# antifamini.net
KiCad netlist of a schematic drawn in EAGLE
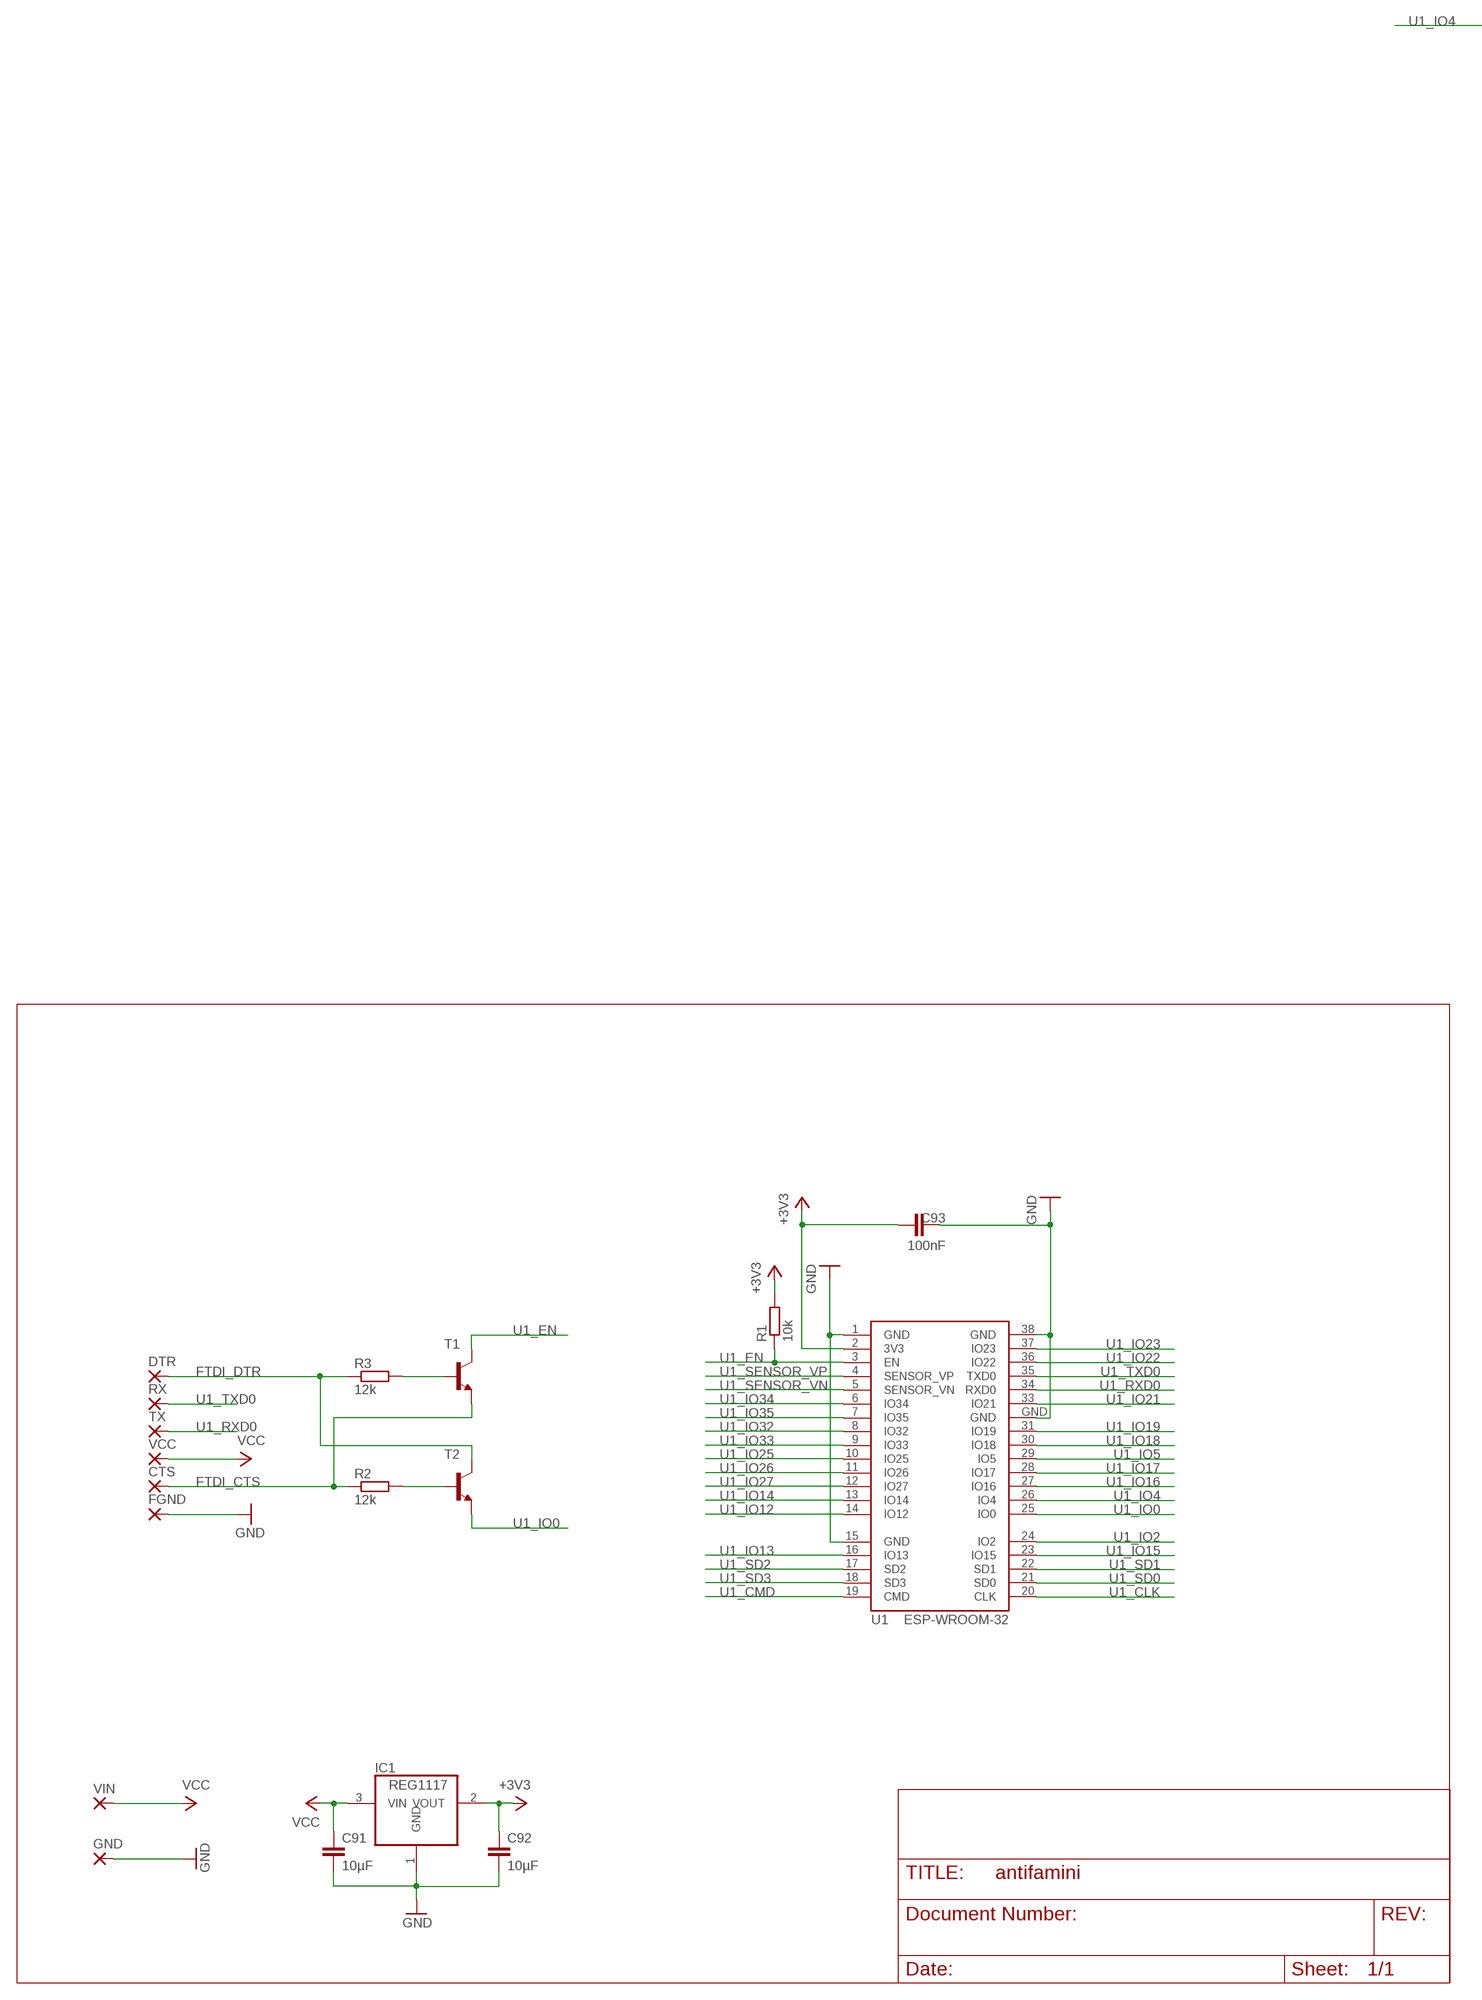
[diagram p0: schematic, sheet 1, part 1 of 2]
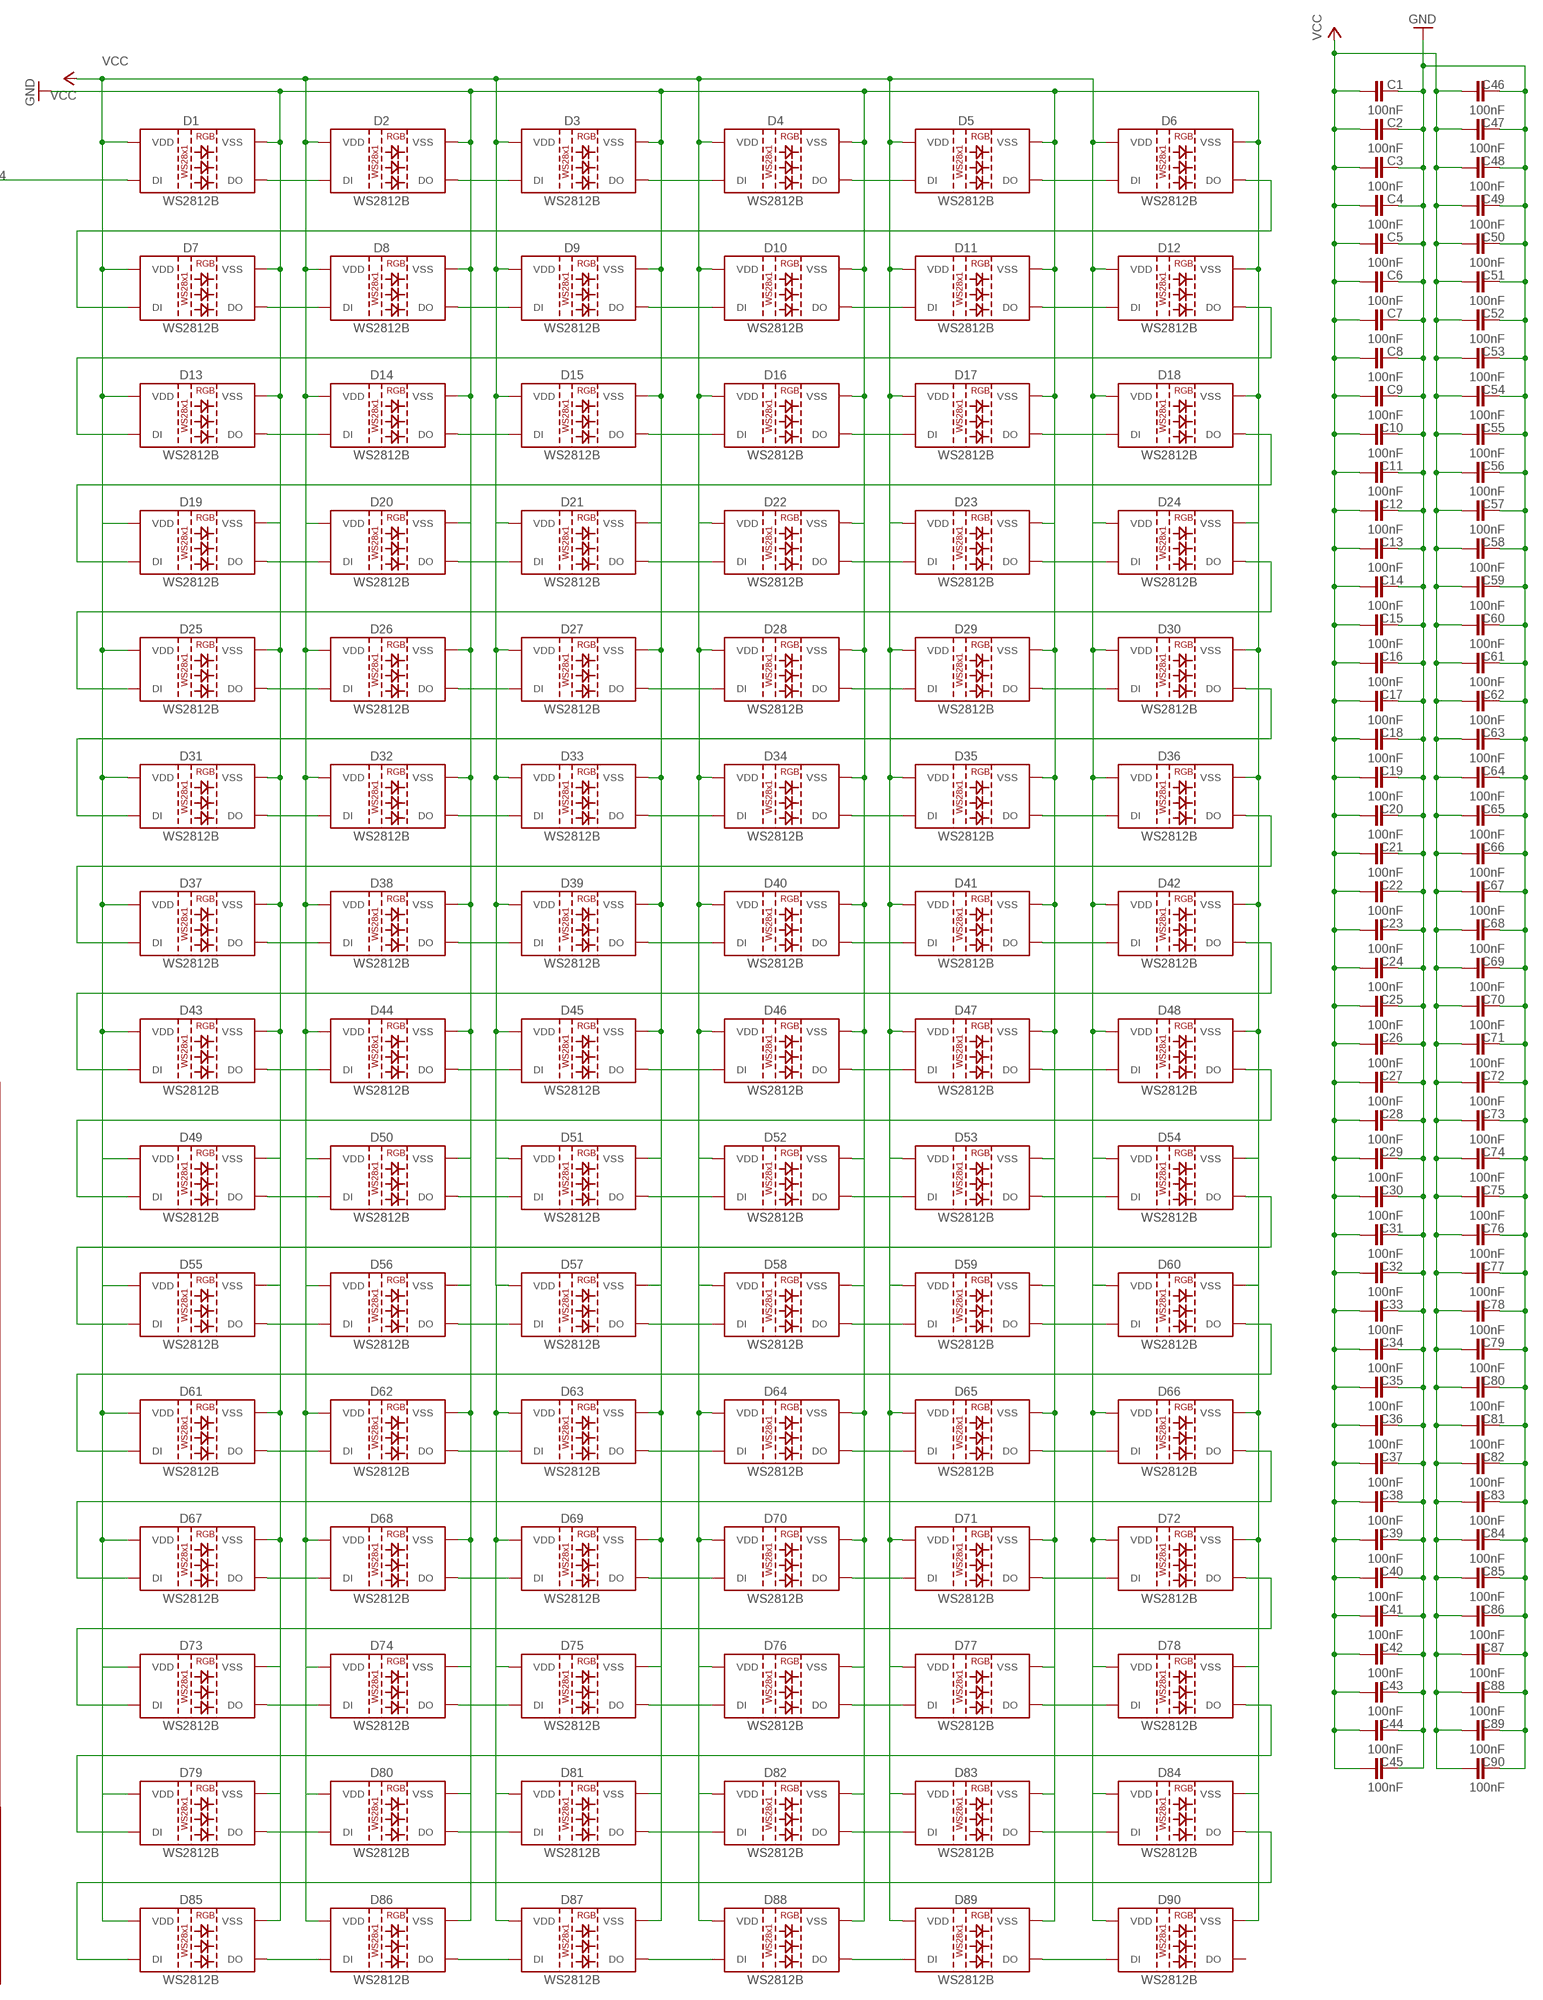
[diagram p1: schematic, sheet 1, part 2 of 2]

(export (version "E")
  (design (tool "Eeschema 10.0.6"))
  (components
    (comp (ref "C1")
      (value "100nF")
      (footprint "eagle-import:C0603")
      (libsource (lib "eagle-import") (part "C-EUC0603"))
    )
    (comp (ref "C2")
      (value "100nF")
      (footprint "eagle-import:C0603")
      (libsource (lib "eagle-import") (part "C-EUC0603"))
    )
    (comp (ref "C3")
      (value "100nF")
      (footprint "eagle-import:C0603")
      (libsource (lib "eagle-import") (part "C-EUC0603"))
    )
    (comp (ref "C4")
      (value "100nF")
      (footprint "eagle-import:C0603")
      (libsource (lib "eagle-import") (part "C-EUC0603"))
    )
    (comp (ref "C5")
      (value "100nF")
      (footprint "eagle-import:C0603")
      (libsource (lib "eagle-import") (part "C-EUC0603"))
    )
    (comp (ref "C6")
      (value "100nF")
      (footprint "eagle-import:C0603")
      (libsource (lib "eagle-import") (part "C-EUC0603"))
    )
    (comp (ref "C7")
      (value "100nF")
      (footprint "eagle-import:C0603")
      (libsource (lib "eagle-import") (part "C-EUC0603"))
    )
    (comp (ref "C8")
      (value "100nF")
      (footprint "eagle-import:C0603")
      (libsource (lib "eagle-import") (part "C-EUC0603"))
    )
    (comp (ref "C9")
      (value "100nF")
      (footprint "eagle-import:C0603")
      (libsource (lib "eagle-import") (part "C-EUC0603"))
    )
    (comp (ref "C10")
      (value "100nF")
      (footprint "eagle-import:C0603")
      (libsource (lib "eagle-import") (part "C-EUC0603"))
    )
    (comp (ref "C11")
      (value "100nF")
      (footprint "eagle-import:C0603")
      (libsource (lib "eagle-import") (part "C-EUC0603"))
    )
    (comp (ref "C12")
      (value "100nF")
      (footprint "eagle-import:C0603")
      (libsource (lib "eagle-import") (part "C-EUC0603"))
    )
    (comp (ref "C13")
      (value "100nF")
      (footprint "eagle-import:C0603")
      (libsource (lib "eagle-import") (part "C-EUC0603"))
    )
    (comp (ref "C14")
      (value "100nF")
      (footprint "eagle-import:C0603")
      (libsource (lib "eagle-import") (part "C-EUC0603"))
    )
    (comp (ref "C15")
      (value "100nF")
      (footprint "eagle-import:C0603")
      (libsource (lib "eagle-import") (part "C-EUC0603"))
    )
    (comp (ref "C16")
      (value "100nF")
      (footprint "eagle-import:C0603")
      (libsource (lib "eagle-import") (part "C-EUC0603"))
    )
    (comp (ref "C17")
      (value "100nF")
      (footprint "eagle-import:C0603")
      (libsource (lib "eagle-import") (part "C-EUC0603"))
    )
    (comp (ref "C18")
      (value "100nF")
      (footprint "eagle-import:C0603")
      (libsource (lib "eagle-import") (part "C-EUC0603"))
    )
    (comp (ref "C19")
      (value "100nF")
      (footprint "eagle-import:C0603")
      (libsource (lib "eagle-import") (part "C-EUC0603"))
    )
    (comp (ref "C20")
      (value "100nF")
      (footprint "eagle-import:C0603")
      (libsource (lib "eagle-import") (part "C-EUC0603"))
    )
    (comp (ref "C21")
      (value "100nF")
      (footprint "eagle-import:C0603")
      (libsource (lib "eagle-import") (part "C-EUC0603"))
    )
    (comp (ref "C22")
      (value "100nF")
      (footprint "eagle-import:C0603")
      (libsource (lib "eagle-import") (part "C-EUC0603"))
    )
    (comp (ref "C23")
      (value "100nF")
      (footprint "eagle-import:C0603")
      (libsource (lib "eagle-import") (part "C-EUC0603"))
    )
    (comp (ref "C24")
      (value "100nF")
      (footprint "eagle-import:C0603")
      (libsource (lib "eagle-import") (part "C-EUC0603"))
    )
    (comp (ref "C25")
      (value "100nF")
      (footprint "eagle-import:C0603")
      (libsource (lib "eagle-import") (part "C-EUC0603"))
    )
    (comp (ref "C26")
      (value "100nF")
      (footprint "eagle-import:C0603")
      (libsource (lib "eagle-import") (part "C-EUC0603"))
    )
    (comp (ref "C27")
      (value "100nF")
      (footprint "eagle-import:C0603")
      (libsource (lib "eagle-import") (part "C-EUC0603"))
    )
    (comp (ref "C28")
      (value "100nF")
      (footprint "eagle-import:C0603")
      (libsource (lib "eagle-import") (part "C-EUC0603"))
    )
    (comp (ref "C29")
      (value "100nF")
      (footprint "eagle-import:C0603")
      (libsource (lib "eagle-import") (part "C-EUC0603"))
    )
    (comp (ref "C30")
      (value "100nF")
      (footprint "eagle-import:C0603")
      (libsource (lib "eagle-import") (part "C-EUC0603"))
    )
    (comp (ref "C31")
      (value "100nF")
      (footprint "eagle-import:C0603")
      (libsource (lib "eagle-import") (part "C-EUC0603"))
    )
    (comp (ref "C32")
      (value "100nF")
      (footprint "eagle-import:C0603")
      (libsource (lib "eagle-import") (part "C-EUC0603"))
    )
    (comp (ref "C33")
      (value "100nF")
      (footprint "eagle-import:C0603")
      (libsource (lib "eagle-import") (part "C-EUC0603"))
    )
    (comp (ref "C34")
      (value "100nF")
      (footprint "eagle-import:C0603")
      (libsource (lib "eagle-import") (part "C-EUC0603"))
    )
    (comp (ref "C35")
      (value "100nF")
      (footprint "eagle-import:C0603")
      (libsource (lib "eagle-import") (part "C-EUC0603"))
    )
    (comp (ref "C36")
      (value "100nF")
      (footprint "eagle-import:C0603")
      (libsource (lib "eagle-import") (part "C-EUC0603"))
    )
    (comp (ref "C37")
      (value "100nF")
      (footprint "eagle-import:C0603")
      (libsource (lib "eagle-import") (part "C-EUC0603"))
    )
    (comp (ref "C38")
      (value "100nF")
      (footprint "eagle-import:C0603")
      (libsource (lib "eagle-import") (part "C-EUC0603"))
    )
    (comp (ref "C39")
      (value "100nF")
      (footprint "eagle-import:C0603")
      (libsource (lib "eagle-import") (part "C-EUC0603"))
    )
    (comp (ref "C40")
      (value "100nF")
      (footprint "eagle-import:C0603")
      (libsource (lib "eagle-import") (part "C-EUC0603"))
    )
    (comp (ref "C41")
      (value "100nF")
      (footprint "eagle-import:C0603")
      (libsource (lib "eagle-import") (part "C-EUC0603"))
    )
    (comp (ref "C42")
      (value "100nF")
      (footprint "eagle-import:C0603")
      (libsource (lib "eagle-import") (part "C-EUC0603"))
    )
    (comp (ref "C43")
      (value "100nF")
      (footprint "eagle-import:C0603")
      (libsource (lib "eagle-import") (part "C-EUC0603"))
    )
    (comp (ref "C44")
      (value "100nF")
      (footprint "eagle-import:C0603")
      (libsource (lib "eagle-import") (part "C-EUC0603"))
    )
    (comp (ref "C45")
      (value "100nF")
      (footprint "eagle-import:C0603")
      (libsource (lib "eagle-import") (part "C-EUC0603"))
    )
    (comp (ref "C46")
      (value "100nF")
      (footprint "eagle-import:C0603")
      (libsource (lib "eagle-import") (part "C-EUC0603"))
    )
    (comp (ref "C47")
      (value "100nF")
      (footprint "eagle-import:C0603")
      (libsource (lib "eagle-import") (part "C-EUC0603"))
    )
    (comp (ref "C48")
      (value "100nF")
      (footprint "eagle-import:C0603")
      (libsource (lib "eagle-import") (part "C-EUC0603"))
    )
    (comp (ref "C49")
      (value "100nF")
      (footprint "eagle-import:C0603")
      (libsource (lib "eagle-import") (part "C-EUC0603"))
    )
    (comp (ref "C50")
      (value "100nF")
      (footprint "eagle-import:C0603")
      (libsource (lib "eagle-import") (part "C-EUC0603"))
    )
    (comp (ref "C51")
      (value "100nF")
      (footprint "eagle-import:C0603")
      (libsource (lib "eagle-import") (part "C-EUC0603"))
    )
    (comp (ref "C52")
      (value "100nF")
      (footprint "eagle-import:C0603")
      (libsource (lib "eagle-import") (part "C-EUC0603"))
    )
    (comp (ref "C53")
      (value "100nF")
      (footprint "eagle-import:C0603")
      (libsource (lib "eagle-import") (part "C-EUC0603"))
    )
    (comp (ref "C54")
      (value "100nF")
      (footprint "eagle-import:C0603")
      (libsource (lib "eagle-import") (part "C-EUC0603"))
    )
    (comp (ref "C55")
      (value "100nF")
      (footprint "eagle-import:C0603")
      (libsource (lib "eagle-import") (part "C-EUC0603"))
    )
    (comp (ref "C56")
      (value "100nF")
      (footprint "eagle-import:C0603")
      (libsource (lib "eagle-import") (part "C-EUC0603"))
    )
    (comp (ref "C57")
      (value "100nF")
      (footprint "eagle-import:C0603")
      (libsource (lib "eagle-import") (part "C-EUC0603"))
    )
    (comp (ref "C58")
      (value "100nF")
      (footprint "eagle-import:C0603")
      (libsource (lib "eagle-import") (part "C-EUC0603"))
    )
    (comp (ref "C59")
      (value "100nF")
      (footprint "eagle-import:C0603")
      (libsource (lib "eagle-import") (part "C-EUC0603"))
    )
    (comp (ref "C60")
      (value "100nF")
      (footprint "eagle-import:C0603")
      (libsource (lib "eagle-import") (part "C-EUC0603"))
    )
    (comp (ref "C61")
      (value "100nF")
      (footprint "eagle-import:C0603")
      (libsource (lib "eagle-import") (part "C-EUC0603"))
    )
    (comp (ref "C62")
      (value "100nF")
      (footprint "eagle-import:C0603")
      (libsource (lib "eagle-import") (part "C-EUC0603"))
    )
    (comp (ref "C63")
      (value "100nF")
      (footprint "eagle-import:C0603")
      (libsource (lib "eagle-import") (part "C-EUC0603"))
    )
    (comp (ref "C64")
      (value "100nF")
      (footprint "eagle-import:C0603")
      (libsource (lib "eagle-import") (part "C-EUC0603"))
    )
    (comp (ref "C65")
      (value "100nF")
      (footprint "eagle-import:C0603")
      (libsource (lib "eagle-import") (part "C-EUC0603"))
    )
    (comp (ref "C66")
      (value "100nF")
      (footprint "eagle-import:C0603")
      (libsource (lib "eagle-import") (part "C-EUC0603"))
    )
    (comp (ref "C67")
      (value "100nF")
      (footprint "eagle-import:C0603")
      (libsource (lib "eagle-import") (part "C-EUC0603"))
    )
    (comp (ref "C68")
      (value "100nF")
      (footprint "eagle-import:C0603")
      (libsource (lib "eagle-import") (part "C-EUC0603"))
    )
    (comp (ref "C69")
      (value "100nF")
      (footprint "eagle-import:C0603")
      (libsource (lib "eagle-import") (part "C-EUC0603"))
    )
    (comp (ref "C70")
      (value "100nF")
      (footprint "eagle-import:C0603")
      (libsource (lib "eagle-import") (part "C-EUC0603"))
    )
    (comp (ref "C71")
      (value "100nF")
      (footprint "eagle-import:C0603")
      (libsource (lib "eagle-import") (part "C-EUC0603"))
    )
    (comp (ref "C72")
      (value "100nF")
      (footprint "eagle-import:C0603")
      (libsource (lib "eagle-import") (part "C-EUC0603"))
    )
    (comp (ref "C73")
      (value "100nF")
      (footprint "eagle-import:C0603")
      (libsource (lib "eagle-import") (part "C-EUC0603"))
    )
    (comp (ref "C74")
      (value "100nF")
      (footprint "eagle-import:C0603")
      (libsource (lib "eagle-import") (part "C-EUC0603"))
    )
    (comp (ref "C75")
      (value "100nF")
      (footprint "eagle-import:C0603")
      (libsource (lib "eagle-import") (part "C-EUC0603"))
    )
    (comp (ref "C76")
      (value "100nF")
      (footprint "eagle-import:C0603")
      (libsource (lib "eagle-import") (part "C-EUC0603"))
    )
    (comp (ref "C77")
      (value "100nF")
      (footprint "eagle-import:C0603")
      (libsource (lib "eagle-import") (part "C-EUC0603"))
    )
    (comp (ref "C78")
      (value "100nF")
      (footprint "eagle-import:C0603")
      (libsource (lib "eagle-import") (part "C-EUC0603"))
    )
    (comp (ref "C79")
      (value "100nF")
      (footprint "eagle-import:C0603")
      (libsource (lib "eagle-import") (part "C-EUC0603"))
    )
    (comp (ref "C80")
      (value "100nF")
      (footprint "eagle-import:C0603")
      (libsource (lib "eagle-import") (part "C-EUC0603"))
    )
    (comp (ref "C81")
      (value "100nF")
      (footprint "eagle-import:C0603")
      (libsource (lib "eagle-import") (part "C-EUC0603"))
    )
    (comp (ref "C82")
      (value "100nF")
      (footprint "eagle-import:C0603")
      (libsource (lib "eagle-import") (part "C-EUC0603"))
    )
    (comp (ref "C83")
      (value "100nF")
      (footprint "eagle-import:C0603")
      (libsource (lib "eagle-import") (part "C-EUC0603"))
    )
    (comp (ref "C84")
      (value "100nF")
      (footprint "eagle-import:C0603")
      (libsource (lib "eagle-import") (part "C-EUC0603"))
    )
    (comp (ref "C85")
      (value "100nF")
      (footprint "eagle-import:C0603")
      (libsource (lib "eagle-import") (part "C-EUC0603"))
    )
    (comp (ref "C86")
      (value "100nF")
      (footprint "eagle-import:C0603")
      (libsource (lib "eagle-import") (part "C-EUC0603"))
    )
    (comp (ref "C87")
      (value "100nF")
      (footprint "eagle-import:C0603")
      (libsource (lib "eagle-import") (part "C-EUC0603"))
    )
    (comp (ref "C88")
      (value "100nF")
      (footprint "eagle-import:C0603")
      (libsource (lib "eagle-import") (part "C-EUC0603"))
    )
    (comp (ref "C89")
      (value "100nF")
      (footprint "eagle-import:C0603")
      (libsource (lib "eagle-import") (part "C-EUC0603"))
    )
    (comp (ref "C90")
      (value "100nF")
      (footprint "eagle-import:C0603")
      (libsource (lib "eagle-import") (part "C-EUC0603"))
    )
    (comp (ref "C91")
      (value "10µF")
      (footprint "eagle-import:C1206K")
      (libsource (lib "eagle-import") (part "C-EUC1206K"))
    )
    (comp (ref "C92")
      (value "10µF")
      (footprint "eagle-import:C1206K")
      (libsource (lib "eagle-import") (part "C-EUC1206K"))
    )
    (comp (ref "C93")
      (value "100nF")
      (footprint "eagle-import:C0603")
      (libsource (lib "eagle-import") (part "C-EUC0603"))
    )
    (comp (ref "CTS")
      (value "SMD2")
      (footprint "eagle-import:SMD1,27-2,54")
      (libsource (lib "eagle-import") (part "SMD2"))
    )
    (comp (ref "D1")
      (value "WS2812B")
      (footprint "eagle-import:WS2812B")
      (libsource (lib "eagle-import") (part "WS2812B"))
    )
    (comp (ref "D2")
      (value "WS2812B")
      (footprint "eagle-import:WS2812B")
      (libsource (lib "eagle-import") (part "WS2812B"))
    )
    (comp (ref "D3")
      (value "WS2812B")
      (footprint "eagle-import:WS2812B")
      (libsource (lib "eagle-import") (part "WS2812B"))
    )
    (comp (ref "D4")
      (value "WS2812B")
      (footprint "eagle-import:WS2812B")
      (libsource (lib "eagle-import") (part "WS2812B"))
    )
    (comp (ref "D5")
      (value "WS2812B")
      (footprint "eagle-import:WS2812B")
      (libsource (lib "eagle-import") (part "WS2812B"))
    )
    (comp (ref "D6")
      (value "WS2812B")
      (footprint "eagle-import:WS2812B")
      (libsource (lib "eagle-import") (part "WS2812B"))
    )
    (comp (ref "D7")
      (value "WS2812B")
      (footprint "eagle-import:WS2812B")
      (libsource (lib "eagle-import") (part "WS2812B"))
    )
    (comp (ref "D8")
      (value "WS2812B")
      (footprint "eagle-import:WS2812B")
      (libsource (lib "eagle-import") (part "WS2812B"))
    )
    (comp (ref "D9")
      (value "WS2812B")
      (footprint "eagle-import:WS2812B")
      (libsource (lib "eagle-import") (part "WS2812B"))
    )
    (comp (ref "D10")
      (value "WS2812B")
      (footprint "eagle-import:WS2812B")
      (libsource (lib "eagle-import") (part "WS2812B"))
    )
    (comp (ref "D11")
      (value "WS2812B")
      (footprint "eagle-import:WS2812B")
      (libsource (lib "eagle-import") (part "WS2812B"))
    )
    (comp (ref "D12")
      (value "WS2812B")
      (footprint "eagle-import:WS2812B")
      (libsource (lib "eagle-import") (part "WS2812B"))
    )
    (comp (ref "D13")
      (value "WS2812B")
      (footprint "eagle-import:WS2812B")
      (libsource (lib "eagle-import") (part "WS2812B"))
    )
    (comp (ref "D14")
      (value "WS2812B")
      (footprint "eagle-import:WS2812B")
      (libsource (lib "eagle-import") (part "WS2812B"))
    )
    (comp (ref "D15")
      (value "WS2812B")
      (footprint "eagle-import:WS2812B")
      (libsource (lib "eagle-import") (part "WS2812B"))
    )
    (comp (ref "D16")
      (value "WS2812B")
      (footprint "eagle-import:WS2812B")
      (libsource (lib "eagle-import") (part "WS2812B"))
    )
    (comp (ref "D17")
      (value "WS2812B")
      (footprint "eagle-import:WS2812B")
      (libsource (lib "eagle-import") (part "WS2812B"))
    )
    (comp (ref "D18")
      (value "WS2812B")
      (footprint "eagle-import:WS2812B")
      (libsource (lib "eagle-import") (part "WS2812B"))
    )
    (comp (ref "D19")
      (value "WS2812B")
      (footprint "eagle-import:WS2812B")
      (libsource (lib "eagle-import") (part "WS2812B"))
    )
    (comp (ref "D20")
      (value "WS2812B")
      (footprint "eagle-import:WS2812B")
      (libsource (lib "eagle-import") (part "WS2812B"))
    )
    (comp (ref "D21")
      (value "WS2812B")
      (footprint "eagle-import:WS2812B")
      (libsource (lib "eagle-import") (part "WS2812B"))
    )
    (comp (ref "D22")
      (value "WS2812B")
      (footprint "eagle-import:WS2812B")
      (libsource (lib "eagle-import") (part "WS2812B"))
    )
    (comp (ref "D23")
      (value "WS2812B")
      (footprint "eagle-import:WS2812B")
      (libsource (lib "eagle-import") (part "WS2812B"))
    )
    (comp (ref "D24")
      (value "WS2812B")
      (footprint "eagle-import:WS2812B")
      (libsource (lib "eagle-import") (part "WS2812B"))
    )
    (comp (ref "D25")
      (value "WS2812B")
      (footprint "eagle-import:WS2812B")
      (libsource (lib "eagle-import") (part "WS2812B"))
    )
    (comp (ref "D26")
      (value "WS2812B")
      (footprint "eagle-import:WS2812B")
      (libsource (lib "eagle-import") (part "WS2812B"))
    )
    (comp (ref "D27")
      (value "WS2812B")
      (footprint "eagle-import:WS2812B")
      (libsource (lib "eagle-import") (part "WS2812B"))
    )
    (comp (ref "D28")
      (value "WS2812B")
      (footprint "eagle-import:WS2812B")
      (libsource (lib "eagle-import") (part "WS2812B"))
    )
    (comp (ref "D29")
      (value "WS2812B")
      (footprint "eagle-import:WS2812B")
      (libsource (lib "eagle-import") (part "WS2812B"))
    )
    (comp (ref "D30")
      (value "WS2812B")
      (footprint "eagle-import:WS2812B")
      (libsource (lib "eagle-import") (part "WS2812B"))
    )
    (comp (ref "D31")
      (value "WS2812B")
      (footprint "eagle-import:WS2812B")
      (libsource (lib "eagle-import") (part "WS2812B"))
    )
    (comp (ref "D32")
      (value "WS2812B")
      (footprint "eagle-import:WS2812B")
      (libsource (lib "eagle-import") (part "WS2812B"))
    )
    (comp (ref "D33")
      (value "WS2812B")
      (footprint "eagle-import:WS2812B")
      (libsource (lib "eagle-import") (part "WS2812B"))
    )
    (comp (ref "D34")
      (value "WS2812B")
      (footprint "eagle-import:WS2812B")
      (libsource (lib "eagle-import") (part "WS2812B"))
    )
    (comp (ref "D35")
      (value "WS2812B")
      (footprint "eagle-import:WS2812B")
      (libsource (lib "eagle-import") (part "WS2812B"))
    )
    (comp (ref "D36")
      (value "WS2812B")
      (footprint "eagle-import:WS2812B")
      (libsource (lib "eagle-import") (part "WS2812B"))
    )
    (comp (ref "D37")
      (value "WS2812B")
      (footprint "eagle-import:WS2812B")
      (libsource (lib "eagle-import") (part "WS2812B"))
    )
    (comp (ref "D38")
      (value "WS2812B")
      (footprint "eagle-import:WS2812B")
      (libsource (lib "eagle-import") (part "WS2812B"))
    )
    (comp (ref "D39")
      (value "WS2812B")
      (footprint "eagle-import:WS2812B")
      (libsource (lib "eagle-import") (part "WS2812B"))
    )
    (comp (ref "D40")
      (value "WS2812B")
      (footprint "eagle-import:WS2812B")
      (libsource (lib "eagle-import") (part "WS2812B"))
    )
    (comp (ref "D41")
      (value "WS2812B")
      (footprint "eagle-import:WS2812B")
      (libsource (lib "eagle-import") (part "WS2812B"))
    )
    (comp (ref "D42")
      (value "WS2812B")
      (footprint "eagle-import:WS2812B")
      (libsource (lib "eagle-import") (part "WS2812B"))
    )
    (comp (ref "D43")
      (value "WS2812B")
      (footprint "eagle-import:WS2812B")
      (libsource (lib "eagle-import") (part "WS2812B"))
    )
    (comp (ref "D44")
      (value "WS2812B")
      (footprint "eagle-import:WS2812B")
      (libsource (lib "eagle-import") (part "WS2812B"))
    )
    (comp (ref "D45")
      (value "WS2812B")
      (footprint "eagle-import:WS2812B")
      (libsource (lib "eagle-import") (part "WS2812B"))
    )
    (comp (ref "D46")
      (value "WS2812B")
      (footprint "eagle-import:WS2812B")
      (libsource (lib "eagle-import") (part "WS2812B"))
    )
    (comp (ref "D47")
      (value "WS2812B")
      (footprint "eagle-import:WS2812B")
      (libsource (lib "eagle-import") (part "WS2812B"))
    )
    (comp (ref "D48")
      (value "WS2812B")
      (footprint "eagle-import:WS2812B")
      (libsource (lib "eagle-import") (part "WS2812B"))
    )
    (comp (ref "D49")
      (value "WS2812B")
      (footprint "eagle-import:WS2812B")
      (libsource (lib "eagle-import") (part "WS2812B"))
    )
    (comp (ref "D50")
      (value "WS2812B")
      (footprint "eagle-import:WS2812B")
      (libsource (lib "eagle-import") (part "WS2812B"))
    )
    (comp (ref "D51")
      (value "WS2812B")
      (footprint "eagle-import:WS2812B")
      (libsource (lib "eagle-import") (part "WS2812B"))
    )
    (comp (ref "D52")
      (value "WS2812B")
      (footprint "eagle-import:WS2812B")
      (libsource (lib "eagle-import") (part "WS2812B"))
    )
    (comp (ref "D53")
      (value "WS2812B")
      (footprint "eagle-import:WS2812B")
      (libsource (lib "eagle-import") (part "WS2812B"))
    )
    (comp (ref "D54")
      (value "WS2812B")
      (footprint "eagle-import:WS2812B")
      (libsource (lib "eagle-import") (part "WS2812B"))
    )
    (comp (ref "D55")
      (value "WS2812B")
      (footprint "eagle-import:WS2812B")
      (libsource (lib "eagle-import") (part "WS2812B"))
    )
    (comp (ref "D56")
      (value "WS2812B")
      (footprint "eagle-import:WS2812B")
      (libsource (lib "eagle-import") (part "WS2812B"))
    )
    (comp (ref "D57")
      (value "WS2812B")
      (footprint "eagle-import:WS2812B")
      (libsource (lib "eagle-import") (part "WS2812B"))
    )
    (comp (ref "D58")
      (value "WS2812B")
      (footprint "eagle-import:WS2812B")
      (libsource (lib "eagle-import") (part "WS2812B"))
    )
    (comp (ref "D59")
      (value "WS2812B")
      (footprint "eagle-import:WS2812B")
      (libsource (lib "eagle-import") (part "WS2812B"))
    )
    (comp (ref "D60")
      (value "WS2812B")
      (footprint "eagle-import:WS2812B")
      (libsource (lib "eagle-import") (part "WS2812B"))
    )
    (comp (ref "D61")
      (value "WS2812B")
      (footprint "eagle-import:WS2812B")
      (libsource (lib "eagle-import") (part "WS2812B"))
    )
    (comp (ref "D62")
      (value "WS2812B")
      (footprint "eagle-import:WS2812B")
      (libsource (lib "eagle-import") (part "WS2812B"))
    )
    (comp (ref "D63")
      (value "WS2812B")
      (footprint "eagle-import:WS2812B")
      (libsource (lib "eagle-import") (part "WS2812B"))
    )
    (comp (ref "D64")
      (value "WS2812B")
      (footprint "eagle-import:WS2812B")
      (libsource (lib "eagle-import") (part "WS2812B"))
    )
    (comp (ref "D65")
      (value "WS2812B")
      (footprint "eagle-import:WS2812B")
      (libsource (lib "eagle-import") (part "WS2812B"))
    )
    (comp (ref "D66")
      (value "WS2812B")
      (footprint "eagle-import:WS2812B")
      (libsource (lib "eagle-import") (part "WS2812B"))
    )
    (comp (ref "D67")
      (value "WS2812B")
      (footprint "eagle-import:WS2812B")
      (libsource (lib "eagle-import") (part "WS2812B"))
    )
    (comp (ref "D68")
      (value "WS2812B")
      (footprint "eagle-import:WS2812B")
      (libsource (lib "eagle-import") (part "WS2812B"))
    )
    (comp (ref "D69")
      (value "WS2812B")
      (footprint "eagle-import:WS2812B")
      (libsource (lib "eagle-import") (part "WS2812B"))
    )
    (comp (ref "D70")
      (value "WS2812B")
      (footprint "eagle-import:WS2812B")
      (libsource (lib "eagle-import") (part "WS2812B"))
    )
    (comp (ref "D71")
      (value "WS2812B")
      (footprint "eagle-import:WS2812B")
      (libsource (lib "eagle-import") (part "WS2812B"))
    )
    (comp (ref "D72")
      (value "WS2812B")
      (footprint "eagle-import:WS2812B")
      (libsource (lib "eagle-import") (part "WS2812B"))
    )
    (comp (ref "D73")
      (value "WS2812B")
      (footprint "eagle-import:WS2812B")
      (libsource (lib "eagle-import") (part "WS2812B"))
    )
    (comp (ref "D74")
      (value "WS2812B")
      (footprint "eagle-import:WS2812B")
      (libsource (lib "eagle-import") (part "WS2812B"))
    )
    (comp (ref "D75")
      (value "WS2812B")
      (footprint "eagle-import:WS2812B")
      (libsource (lib "eagle-import") (part "WS2812B"))
    )
    (comp (ref "D76")
      (value "WS2812B")
      (footprint "eagle-import:WS2812B")
      (libsource (lib "eagle-import") (part "WS2812B"))
    )
    (comp (ref "D77")
      (value "WS2812B")
      (footprint "eagle-import:WS2812B")
      (libsource (lib "eagle-import") (part "WS2812B"))
    )
    (comp (ref "D78")
      (value "WS2812B")
      (footprint "eagle-import:WS2812B")
      (libsource (lib "eagle-import") (part "WS2812B"))
    )
    (comp (ref "D79")
      (value "WS2812B")
      (footprint "eagle-import:WS2812B")
      (libsource (lib "eagle-import") (part "WS2812B"))
    )
    (comp (ref "D80")
      (value "WS2812B")
      (footprint "eagle-import:WS2812B")
      (libsource (lib "eagle-import") (part "WS2812B"))
    )
    (comp (ref "D81")
      (value "WS2812B")
      (footprint "eagle-import:WS2812B")
      (libsource (lib "eagle-import") (part "WS2812B"))
    )
    (comp (ref "D82")
      (value "WS2812B")
      (footprint "eagle-import:WS2812B")
      (libsource (lib "eagle-import") (part "WS2812B"))
    )
    (comp (ref "D83")
      (value "WS2812B")
      (footprint "eagle-import:WS2812B")
      (libsource (lib "eagle-import") (part "WS2812B"))
    )
    (comp (ref "D84")
      (value "WS2812B")
      (footprint "eagle-import:WS2812B")
      (libsource (lib "eagle-import") (part "WS2812B"))
    )
    (comp (ref "D85")
      (value "WS2812B")
      (footprint "eagle-import:WS2812B")
      (libsource (lib "eagle-import") (part "WS2812B"))
    )
    (comp (ref "D86")
      (value "WS2812B")
      (footprint "eagle-import:WS2812B")
      (libsource (lib "eagle-import") (part "WS2812B"))
    )
    (comp (ref "D87")
      (value "WS2812B")
      (footprint "eagle-import:WS2812B")
      (libsource (lib "eagle-import") (part "WS2812B"))
    )
    (comp (ref "D88")
      (value "WS2812B")
      (footprint "eagle-import:WS2812B")
      (libsource (lib "eagle-import") (part "WS2812B"))
    )
    (comp (ref "D89")
      (value "WS2812B")
      (footprint "eagle-import:WS2812B")
      (libsource (lib "eagle-import") (part "WS2812B"))
    )
    (comp (ref "D90")
      (value "WS2812B")
      (footprint "eagle-import:WS2812B")
      (libsource (lib "eagle-import") (part "WS2812B"))
    )
    (comp (ref "DTR")
      (value "SMD2")
      (footprint "eagle-import:SMD1,27-2,54")
      (libsource (lib "eagle-import") (part "SMD2"))
    )
    (comp (ref "FGND")
      (value "SMD2")
      (footprint "eagle-import:SMD1,27-2,54")
      (libsource (lib "eagle-import") (part "SMD2"))
    )
    (comp (ref "GND")
      (value "SMD5")
      (footprint "eagle-import:SMD2,54-5,08")
      (libsource (lib "eagle-import") (part "SMD5"))
    )
    (comp (ref "IC1")
      (value "REG1117")
      (footprint "eagle-import:SOT223")
      (libsource (lib "eagle-import") (part "REG1117"))
    )
    (comp (ref "R1")
      (value "10k")
      (footprint "eagle-import:R0603")
      (libsource (lib "eagle-import") (part "R-EU_R0603"))
    )
    (comp (ref "R2")
      (value "12k")
      (footprint "eagle-import:R0603")
      (libsource (lib "eagle-import") (part "R-EU_R0603"))
    )
    (comp (ref "R3")
      (value "12k")
      (footprint "eagle-import:R0603")
      (libsource (lib "eagle-import") (part "R-EU_R0603"))
    )
    (comp (ref "RX")
      (value "SMD2")
      (footprint "eagle-import:SMD1,27-2,54")
      (libsource (lib "eagle-import") (part "SMD2"))
    )
    (comp (ref "T1")
      (value "BC818-40-NPN-SOT23-BEC")
      (footprint "eagle-import:SOT23-BEC")
      (libsource (lib "eagle-import") (part "-NPN-SOT23-BECBC818-40"))
    )
    (comp (ref "T2")
      (value "BC818-40-NPN-SOT23-BEC")
      (footprint "eagle-import:SOT23-BEC")
      (libsource (lib "eagle-import") (part "-NPN-SOT23-BECBC818-40"))
    )
    (comp (ref "TX")
      (value "SMD2")
      (footprint "eagle-import:SMD1,27-2,54")
      (libsource (lib "eagle-import") (part "SMD2"))
    )
    (comp (ref "U1")
      (value "ESP-WROOM-32")
      (footprint "eagle-import:ESP-WROOM-32")
      (libsource (lib "eagle-import") (part "ESP-WROOM-32"))
    )
    (comp (ref "VCC")
      (value "SMD2")
      (footprint "eagle-import:SMD1,27-2,54")
      (libsource (lib "eagle-import") (part "SMD2"))
    )
    (comp (ref "VIN")
      (value "SMD5")
      (footprint "eagle-import:SMD2,54-5,08")
      (libsource (lib "eagle-import") (part "SMD5"))
    )
  )
  (nets
    (net (code "1") (name "+3V3") (class "Default")
      (node (ref "C92") (pin "1") (pinfunction "1_1") (pintype "passive"))
      (node (ref "C93") (pin "2") (pinfunction "2_2") (pintype "passive"))
      (node (ref "IC1") (pin "2") (pinfunction "VOUT_2") (pintype "output"))
      (node (ref "R1") (pin "2") (pinfunction "2_2") (pintype "passive"))
      (node (ref "U1") (pin "2") (pinfunction "3V3_2") (pintype "power_in"))
    )
    (net (code "2") (name "/FTDI_CTS") (class "Default")
      (node (ref "CTS") (pin "1") (pinfunction "P_1") (pintype "passive"))
      (node (ref "R2") (pin "1") (pinfunction "1_1") (pintype "passive"))
      (node (ref "T1") (pin "E") (pinfunction "E_E") (pintype "passive"))
    )
    (net (code "3") (name "/FTDI_DTR") (class "Default")
      (node (ref "DTR") (pin "1") (pinfunction "P_1") (pintype "passive"))
      (node (ref "R3") (pin "1") (pinfunction "1_1") (pintype "passive"))
      (node (ref "T2") (pin "C") (pinfunction "C_C") (pintype "passive"))
    )
    (net (code "4") (name "/U1_CLK") (class "Default")
      (node (ref "U1") (pin "20") (pinfunction "CLK_20") (pintype "bidirectional"))
    )
    (net (code "5") (name "/U1_CMD") (class "Default")
      (node (ref "U1") (pin "19") (pinfunction "CMD_19") (pintype "bidirectional"))
    )
    (net (code "6") (name "/U1_EN") (class "Default")
      (node (ref "R1") (pin "1") (pinfunction "1_1") (pintype "passive"))
      (node (ref "T1") (pin "C") (pinfunction "C_C") (pintype "passive"))
      (node (ref "U1") (pin "3") (pinfunction "EN_3") (pintype "input"))
    )
    (net (code "7") (name "/U1_IO0") (class "Default")
      (node (ref "T2") (pin "E") (pinfunction "E_E") (pintype "passive"))
      (node (ref "U1") (pin "25") (pinfunction "IO0_25") (pintype "bidirectional"))
    )
    (net (code "8") (name "/U1_IO2") (class "Default")
      (node (ref "U1") (pin "24") (pinfunction "IO2_24") (pintype "bidirectional"))
    )
    (net (code "9") (name "/U1_IO4") (class "Default")
      (node (ref "D1") (pin "4") (pinfunction "DI_4") (pintype "bidirectional"))
      (node (ref "U1") (pin "26") (pinfunction "IO4_26") (pintype "bidirectional"))
    )
    (net (code "10") (name "/U1_IO5") (class "Default")
      (node (ref "U1") (pin "29") (pinfunction "IO5_29") (pintype "bidirectional"))
    )
    (net (code "11") (name "/U1_IO12") (class "Default")
      (node (ref "U1") (pin "14") (pinfunction "IO12_14") (pintype "bidirectional"))
    )
    (net (code "12") (name "/U1_IO13") (class "Default")
      (node (ref "U1") (pin "16") (pinfunction "IO13_16") (pintype "bidirectional"))
    )
    (net (code "13") (name "/U1_IO14") (class "Default")
      (node (ref "U1") (pin "13") (pinfunction "IO14_13") (pintype "bidirectional"))
    )
    (net (code "14") (name "/U1_IO15") (class "Default")
      (node (ref "U1") (pin "23") (pinfunction "IO15_23") (pintype "bidirectional"))
    )
    (net (code "15") (name "/U1_IO16") (class "Default")
      (node (ref "U1") (pin "27") (pinfunction "IO16_27") (pintype "bidirectional"))
    )
    (net (code "16") (name "/U1_IO17") (class "Default")
      (node (ref "U1") (pin "28") (pinfunction "IO17_28") (pintype "bidirectional"))
    )
    (net (code "17") (name "/U1_IO18") (class "Default")
      (node (ref "U1") (pin "30") (pinfunction "IO18_30") (pintype "bidirectional"))
    )
    (net (code "18") (name "/U1_IO19") (class "Default")
      (node (ref "U1") (pin "31") (pinfunction "IO19_31") (pintype "bidirectional"))
    )
    (net (code "19") (name "/U1_IO21") (class "Default")
      (node (ref "U1") (pin "33") (pinfunction "IO21_33") (pintype "bidirectional"))
    )
    (net (code "20") (name "/U1_IO22") (class "Default")
      (node (ref "U1") (pin "36") (pinfunction "IO22_36") (pintype "bidirectional"))
    )
    (net (code "21") (name "/U1_IO23") (class "Default")
      (node (ref "U1") (pin "37") (pinfunction "IO23_37") (pintype "bidirectional"))
    )
    (net (code "22") (name "/U1_IO25") (class "Default")
      (node (ref "U1") (pin "10") (pinfunction "IO25_10") (pintype "bidirectional"))
    )
    (net (code "23") (name "/U1_IO26") (class "Default")
      (node (ref "U1") (pin "11") (pinfunction "IO26_11") (pintype "bidirectional"))
    )
    (net (code "24") (name "/U1_IO27") (class "Default")
      (node (ref "U1") (pin "12") (pinfunction "IO27_12") (pintype "bidirectional"))
    )
    (net (code "25") (name "/U1_IO32") (class "Default")
      (node (ref "U1") (pin "8") (pinfunction "IO32_8") (pintype "bidirectional"))
    )
    (net (code "26") (name "/U1_IO33") (class "Default")
      (node (ref "U1") (pin "9") (pinfunction "IO33_9") (pintype "bidirectional"))
    )
    (net (code "27") (name "/U1_IO34") (class "Default")
      (node (ref "U1") (pin "6") (pinfunction "IO34_6") (pintype "bidirectional"))
    )
    (net (code "28") (name "/U1_IO35") (class "Default")
      (node (ref "U1") (pin "7") (pinfunction "IO35_7") (pintype "bidirectional"))
    )
    (net (code "29") (name "/U1_RXD0") (class "Default")
      (node (ref "TX") (pin "1") (pinfunction "P_1") (pintype "passive"))
      (node (ref "U1") (pin "34") (pinfunction "RXD0_34") (pintype "bidirectional"))
    )
    (net (code "30") (name "/U1_SD0") (class "Default")
      (node (ref "U1") (pin "21") (pinfunction "SD0_21") (pintype "bidirectional"))
    )
    (net (code "31") (name "/U1_SD1") (class "Default")
      (node (ref "U1") (pin "22") (pinfunction "SD1_22") (pintype "bidirectional"))
    )
    (net (code "32") (name "/U1_SD2") (class "Default")
      (node (ref "U1") (pin "17") (pinfunction "SD2_17") (pintype "bidirectional"))
    )
    (net (code "33") (name "/U1_SD3") (class "Default")
      (node (ref "U1") (pin "18") (pinfunction "SD3_18") (pintype "bidirectional"))
    )
    (net (code "34") (name "/U1_SENSOR_VN") (class "Default")
      (node (ref "U1") (pin "5") (pinfunction "SENSOR_VN_5") (pintype "bidirectional"))
    )
    (net (code "35") (name "/U1_SENSOR_VP") (class "Default")
      (node (ref "U1") (pin "4") (pinfunction "SENSOR_VP_4") (pintype "bidirectional"))
    )
    (net (code "36") (name "/U1_TXD0") (class "Default")
      (node (ref "RX") (pin "1") (pinfunction "P_1") (pintype "passive"))
      (node (ref "U1") (pin "35") (pinfunction "TXD0_35") (pintype "bidirectional"))
    )
    (net (code "37") (name "GND") (class "Default")
      (node (ref "C1") (pin "1") (pinfunction "1_1") (pintype "passive"))
      (node (ref "C10") (pin "1") (pinfunction "1_1") (pintype "passive"))
      (node (ref "C11") (pin "1") (pinfunction "1_1") (pintype "passive"))
      (node (ref "C12") (pin "1") (pinfunction "1_1") (pintype "passive"))
      (node (ref "C13") (pin "1") (pinfunction "1_1") (pintype "passive"))
      (node (ref "C14") (pin "1") (pinfunction "1_1") (pintype "passive"))
      (node (ref "C15") (pin "1") (pinfunction "1_1") (pintype "passive"))
      (node (ref "C16") (pin "1") (pinfunction "1_1") (pintype "passive"))
      (node (ref "C17") (pin "1") (pinfunction "1_1") (pintype "passive"))
      (node (ref "C18") (pin "1") (pinfunction "1_1") (pintype "passive"))
      (node (ref "C19") (pin "1") (pinfunction "1_1") (pintype "passive"))
      (node (ref "C2") (pin "1") (pinfunction "1_1") (pintype "passive"))
      (node (ref "C20") (pin "1") (pinfunction "1_1") (pintype "passive"))
      (node (ref "C21") (pin "1") (pinfunction "1_1") (pintype "passive"))
      (node (ref "C22") (pin "1") (pinfunction "1_1") (pintype "passive"))
      (node (ref "C23") (pin "1") (pinfunction "1_1") (pintype "passive"))
      (node (ref "C24") (pin "1") (pinfunction "1_1") (pintype "passive"))
      (node (ref "C25") (pin "1") (pinfunction "1_1") (pintype "passive"))
      (node (ref "C26") (pin "1") (pinfunction "1_1") (pintype "passive"))
      (node (ref "C27") (pin "1") (pinfunction "1_1") (pintype "passive"))
      (node (ref "C28") (pin "1") (pinfunction "1_1") (pintype "passive"))
      (node (ref "C29") (pin "1") (pinfunction "1_1") (pintype "passive"))
      (node (ref "C3") (pin "1") (pinfunction "1_1") (pintype "passive"))
      (node (ref "C30") (pin "1") (pinfunction "1_1") (pintype "passive"))
      (node (ref "C31") (pin "1") (pinfunction "1_1") (pintype "passive"))
      (node (ref "C32") (pin "1") (pinfunction "1_1") (pintype "passive"))
      (node (ref "C33") (pin "1") (pinfunction "1_1") (pintype "passive"))
      (node (ref "C34") (pin "1") (pinfunction "1_1") (pintype "passive"))
      (node (ref "C35") (pin "1") (pinfunction "1_1") (pintype "passive"))
      (node (ref "C36") (pin "1") (pinfunction "1_1") (pintype "passive"))
      (node (ref "C37") (pin "1") (pinfunction "1_1") (pintype "passive"))
      (node (ref "C38") (pin "1") (pinfunction "1_1") (pintype "passive"))
      (node (ref "C39") (pin "1") (pinfunction "1_1") (pintype "passive"))
      (node (ref "C4") (pin "1") (pinfunction "1_1") (pintype "passive"))
      (node (ref "C40") (pin "1") (pinfunction "1_1") (pintype "passive"))
      (node (ref "C41") (pin "1") (pinfunction "1_1") (pintype "passive"))
      (node (ref "C42") (pin "1") (pinfunction "1_1") (pintype "passive"))
      (node (ref "C43") (pin "1") (pinfunction "1_1") (pintype "passive"))
      (node (ref "C44") (pin "1") (pinfunction "1_1") (pintype "passive"))
      (node (ref "C45") (pin "1") (pinfunction "1_1") (pintype "passive"))
      (node (ref "C46") (pin "1") (pinfunction "1_1") (pintype "passive"))
      (node (ref "C47") (pin "1") (pinfunction "1_1") (pintype "passive"))
      (node (ref "C48") (pin "1") (pinfunction "1_1") (pintype "passive"))
      (node (ref "C49") (pin "1") (pinfunction "1_1") (pintype "passive"))
      (node (ref "C5") (pin "1") (pinfunction "1_1") (pintype "passive"))
      (node (ref "C50") (pin "1") (pinfunction "1_1") (pintype "passive"))
      (node (ref "C51") (pin "1") (pinfunction "1_1") (pintype "passive"))
      (node (ref "C52") (pin "1") (pinfunction "1_1") (pintype "passive"))
      (node (ref "C53") (pin "1") (pinfunction "1_1") (pintype "passive"))
      (node (ref "C54") (pin "1") (pinfunction "1_1") (pintype "passive"))
      (node (ref "C55") (pin "1") (pinfunction "1_1") (pintype "passive"))
      (node (ref "C56") (pin "1") (pinfunction "1_1") (pintype "passive"))
      (node (ref "C57") (pin "1") (pinfunction "1_1") (pintype "passive"))
      (node (ref "C58") (pin "1") (pinfunction "1_1") (pintype "passive"))
      (node (ref "C59") (pin "1") (pinfunction "1_1") (pintype "passive"))
      (node (ref "C6") (pin "1") (pinfunction "1_1") (pintype "passive"))
      (node (ref "C60") (pin "1") (pinfunction "1_1") (pintype "passive"))
      (node (ref "C61") (pin "1") (pinfunction "1_1") (pintype "passive"))
      (node (ref "C62") (pin "1") (pinfunction "1_1") (pintype "passive"))
      (node (ref "C63") (pin "1") (pinfunction "1_1") (pintype "passive"))
      (node (ref "C64") (pin "1") (pinfunction "1_1") (pintype "passive"))
      (node (ref "C65") (pin "1") (pinfunction "1_1") (pintype "passive"))
      (node (ref "C66") (pin "1") (pinfunction "1_1") (pintype "passive"))
      (node (ref "C67") (pin "1") (pinfunction "1_1") (pintype "passive"))
      (node (ref "C68") (pin "1") (pinfunction "1_1") (pintype "passive"))
      (node (ref "C69") (pin "1") (pinfunction "1_1") (pintype "passive"))
      (node (ref "C7") (pin "1") (pinfunction "1_1") (pintype "passive"))
      (node (ref "C70") (pin "1") (pinfunction "1_1") (pintype "passive"))
      (node (ref "C71") (pin "1") (pinfunction "1_1") (pintype "passive"))
      (node (ref "C72") (pin "1") (pinfunction "1_1") (pintype "passive"))
      (node (ref "C73") (pin "1") (pinfunction "1_1") (pintype "passive"))
      (node (ref "C74") (pin "1") (pinfunction "1_1") (pintype "passive"))
      (node (ref "C75") (pin "1") (pinfunction "1_1") (pintype "passive"))
      (node (ref "C76") (pin "1") (pinfunction "1_1") (pintype "passive"))
      (node (ref "C77") (pin "1") (pinfunction "1_1") (pintype "passive"))
      (node (ref "C78") (pin "1") (pinfunction "1_1") (pintype "passive"))
      (node (ref "C79") (pin "1") (pinfunction "1_1") (pintype "passive"))
      (node (ref "C8") (pin "1") (pinfunction "1_1") (pintype "passive"))
      (node (ref "C80") (pin "1") (pinfunction "1_1") (pintype "passive"))
      (node (ref "C81") (pin "1") (pinfunction "1_1") (pintype "passive"))
      (node (ref "C82") (pin "1") (pinfunction "1_1") (pintype "passive"))
      (node (ref "C83") (pin "1") (pinfunction "1_1") (pintype "passive"))
      (node (ref "C84") (pin "1") (pinfunction "1_1") (pintype "passive"))
      (node (ref "C85") (pin "1") (pinfunction "1_1") (pintype "passive"))
      (node (ref "C86") (pin "1") (pinfunction "1_1") (pintype "passive"))
      (node (ref "C87") (pin "1") (pinfunction "1_1") (pintype "passive"))
      (node (ref "C88") (pin "1") (pinfunction "1_1") (pintype "passive"))
      (node (ref "C89") (pin "1") (pinfunction "1_1") (pintype "passive"))
      (node (ref "C9") (pin "1") (pinfunction "1_1") (pintype "passive"))
      (node (ref "C90") (pin "1") (pinfunction "1_1") (pintype "passive"))
      (node (ref "C91") (pin "2") (pinfunction "2_2") (pintype "passive"))
      (node (ref "C92") (pin "2") (pinfunction "2_2") (pintype "passive"))
      (node (ref "C93") (pin "1") (pinfunction "1_1") (pintype "passive"))
      (node (ref "D1") (pin "3") (pinfunction "VSS_3") (pintype "bidirectional"))
      (node (ref "D10") (pin "3") (pinfunction "VSS_3") (pintype "bidirectional"))
      (node (ref "D11") (pin "3") (pinfunction "VSS_3") (pintype "bidirectional"))
      (node (ref "D12") (pin "3") (pinfunction "VSS_3") (pintype "bidirectional"))
      (node (ref "D13") (pin "3") (pinfunction "VSS_3") (pintype "bidirectional"))
      (node (ref "D14") (pin "3") (pinfunction "VSS_3") (pintype "bidirectional"))
      (node (ref "D15") (pin "3") (pinfunction "VSS_3") (pintype "bidirectional"))
      (node (ref "D16") (pin "3") (pinfunction "VSS_3") (pintype "bidirectional"))
      (node (ref "D17") (pin "3") (pinfunction "VSS_3") (pintype "bidirectional"))
      (node (ref "D18") (pin "3") (pinfunction "VSS_3") (pintype "bidirectional"))
      (node (ref "D19") (pin "3") (pinfunction "VSS_3") (pintype "bidirectional"))
      (node (ref "D2") (pin "3") (pinfunction "VSS_3") (pintype "bidirectional"))
      (node (ref "D20") (pin "3") (pinfunction "VSS_3") (pintype "bidirectional"))
      (node (ref "D21") (pin "3") (pinfunction "VSS_3") (pintype "bidirectional"))
      (node (ref "D22") (pin "3") (pinfunction "VSS_3") (pintype "bidirectional"))
      (node (ref "D23") (pin "3") (pinfunction "VSS_3") (pintype "bidirectional"))
      (node (ref "D24") (pin "3") (pinfunction "VSS_3") (pintype "bidirectional"))
      (node (ref "D25") (pin "3") (pinfunction "VSS_3") (pintype "bidirectional"))
      (node (ref "D26") (pin "3") (pinfunction "VSS_3") (pintype "bidirectional"))
      (node (ref "D27") (pin "3") (pinfunction "VSS_3") (pintype "bidirectional"))
      (node (ref "D28") (pin "3") (pinfunction "VSS_3") (pintype "bidirectional"))
      (node (ref "D29") (pin "3") (pinfunction "VSS_3") (pintype "bidirectional"))
      (node (ref "D3") (pin "3") (pinfunction "VSS_3") (pintype "bidirectional"))
      (node (ref "D30") (pin "3") (pinfunction "VSS_3") (pintype "bidirectional"))
      (node (ref "D31") (pin "3") (pinfunction "VSS_3") (pintype "bidirectional"))
      (node (ref "D32") (pin "3") (pinfunction "VSS_3") (pintype "bidirectional"))
      (node (ref "D33") (pin "3") (pinfunction "VSS_3") (pintype "bidirectional"))
      (node (ref "D34") (pin "3") (pinfunction "VSS_3") (pintype "bidirectional"))
      (node (ref "D35") (pin "3") (pinfunction "VSS_3") (pintype "bidirectional"))
      (node (ref "D36") (pin "3") (pinfunction "VSS_3") (pintype "bidirectional"))
      (node (ref "D37") (pin "3") (pinfunction "VSS_3") (pintype "bidirectional"))
      (node (ref "D38") (pin "3") (pinfunction "VSS_3") (pintype "bidirectional"))
      (node (ref "D39") (pin "3") (pinfunction "VSS_3") (pintype "bidirectional"))
      (node (ref "D4") (pin "3") (pinfunction "VSS_3") (pintype "bidirectional"))
      (node (ref "D40") (pin "3") (pinfunction "VSS_3") (pintype "bidirectional"))
      (node (ref "D41") (pin "3") (pinfunction "VSS_3") (pintype "bidirectional"))
      (node (ref "D42") (pin "3") (pinfunction "VSS_3") (pintype "bidirectional"))
      (node (ref "D43") (pin "3") (pinfunction "VSS_3") (pintype "bidirectional"))
      (node (ref "D44") (pin "3") (pinfunction "VSS_3") (pintype "bidirectional"))
      (node (ref "D45") (pin "3") (pinfunction "VSS_3") (pintype "bidirectional"))
      (node (ref "D46") (pin "3") (pinfunction "VSS_3") (pintype "bidirectional"))
      (node (ref "D47") (pin "3") (pinfunction "VSS_3") (pintype "bidirectional"))
      (node (ref "D48") (pin "3") (pinfunction "VSS_3") (pintype "bidirectional"))
      (node (ref "D49") (pin "3") (pinfunction "VSS_3") (pintype "bidirectional"))
      (node (ref "D5") (pin "3") (pinfunction "VSS_3") (pintype "bidirectional"))
      (node (ref "D50") (pin "3") (pinfunction "VSS_3") (pintype "bidirectional"))
      (node (ref "D51") (pin "3") (pinfunction "VSS_3") (pintype "bidirectional"))
      (node (ref "D52") (pin "3") (pinfunction "VSS_3") (pintype "bidirectional"))
      (node (ref "D53") (pin "3") (pinfunction "VSS_3") (pintype "bidirectional"))
      (node (ref "D54") (pin "3") (pinfunction "VSS_3") (pintype "bidirectional"))
      (node (ref "D55") (pin "3") (pinfunction "VSS_3") (pintype "bidirectional"))
      (node (ref "D56") (pin "3") (pinfunction "VSS_3") (pintype "bidirectional"))
      (node (ref "D57") (pin "3") (pinfunction "VSS_3") (pintype "bidirectional"))
      (node (ref "D58") (pin "3") (pinfunction "VSS_3") (pintype "bidirectional"))
      (node (ref "D59") (pin "3") (pinfunction "VSS_3") (pintype "bidirectional"))
      (node (ref "D6") (pin "3") (pinfunction "VSS_3") (pintype "bidirectional"))
      (node (ref "D60") (pin "3") (pinfunction "VSS_3") (pintype "bidirectional"))
      (node (ref "D61") (pin "3") (pinfunction "VSS_3") (pintype "bidirectional"))
      (node (ref "D62") (pin "3") (pinfunction "VSS_3") (pintype "bidirectional"))
      (node (ref "D63") (pin "3") (pinfunction "VSS_3") (pintype "bidirectional"))
      (node (ref "D64") (pin "3") (pinfunction "VSS_3") (pintype "bidirectional"))
      (node (ref "D65") (pin "3") (pinfunction "VSS_3") (pintype "bidirectional"))
      (node (ref "D66") (pin "3") (pinfunction "VSS_3") (pintype "bidirectional"))
      (node (ref "D67") (pin "3") (pinfunction "VSS_3") (pintype "bidirectional"))
      (node (ref "D68") (pin "3") (pinfunction "VSS_3") (pintype "bidirectional"))
      (node (ref "D69") (pin "3") (pinfunction "VSS_3") (pintype "bidirectional"))
      (node (ref "D7") (pin "3") (pinfunction "VSS_3") (pintype "bidirectional"))
      (node (ref "D70") (pin "3") (pinfunction "VSS_3") (pintype "bidirectional"))
      (node (ref "D71") (pin "3") (pinfunction "VSS_3") (pintype "bidirectional"))
      (node (ref "D72") (pin "3") (pinfunction "VSS_3") (pintype "bidirectional"))
      (node (ref "D73") (pin "3") (pinfunction "VSS_3") (pintype "bidirectional"))
      (node (ref "D74") (pin "3") (pinfunction "VSS_3") (pintype "bidirectional"))
      (node (ref "D75") (pin "3") (pinfunction "VSS_3") (pintype "bidirectional"))
      (node (ref "D76") (pin "3") (pinfunction "VSS_3") (pintype "bidirectional"))
      (node (ref "D77") (pin "3") (pinfunction "VSS_3") (pintype "bidirectional"))
      (node (ref "D78") (pin "3") (pinfunction "VSS_3") (pintype "bidirectional"))
      (node (ref "D79") (pin "3") (pinfunction "VSS_3") (pintype "bidirectional"))
      (node (ref "D8") (pin "3") (pinfunction "VSS_3") (pintype "bidirectional"))
      (node (ref "D80") (pin "3") (pinfunction "VSS_3") (pintype "bidirectional"))
      (node (ref "D81") (pin "3") (pinfunction "VSS_3") (pintype "bidirectional"))
      (node (ref "D82") (pin "3") (pinfunction "VSS_3") (pintype "bidirectional"))
      (node (ref "D83") (pin "3") (pinfunction "VSS_3") (pintype "bidirectional"))
      (node (ref "D84") (pin "3") (pinfunction "VSS_3") (pintype "bidirectional"))
      (node (ref "D85") (pin "3") (pinfunction "VSS_3") (pintype "bidirectional"))
      (node (ref "D86") (pin "3") (pinfunction "VSS_3") (pintype "bidirectional"))
      (node (ref "D87") (pin "3") (pinfunction "VSS_3") (pintype "bidirectional"))
      (node (ref "D88") (pin "3") (pinfunction "VSS_3") (pintype "bidirectional"))
      (node (ref "D89") (pin "3") (pinfunction "VSS_3") (pintype "bidirectional"))
      (node (ref "D9") (pin "3") (pinfunction "VSS_3") (pintype "bidirectional"))
      (node (ref "D90") (pin "3") (pinfunction "VSS_3") (pintype "bidirectional"))
      (node (ref "FGND") (pin "1") (pinfunction "P_1") (pintype "passive"))
      (node (ref "GND") (pin "1") (pinfunction "P_1") (pintype "passive"))
      (node (ref "IC1") (pin "1") (pinfunction "GND_1") (pintype "power_in"))
      (node (ref "U1") (pin "1") (pinfunction "GND_1") (pintype "power_in"))
      (node (ref "U1") (pin "15") (pinfunction "GND_15") (pintype "power_in"))
      (node (ref "U1") (pin "38") (pinfunction "GND_38") (pintype "power_in"))
      (node (ref "U1") (pin "GND") (pinfunction "GND_GND") (pintype "power_in"))
    )
    (net (code "38") (name "Net-(D1-DO)") (class "Default")
      (node (ref "D1") (pin "2") (pinfunction "DO_2") (pintype "bidirectional"))
      (node (ref "D2") (pin "4") (pinfunction "DI_4") (pintype "bidirectional"))
    )
    (net (code "39") (name "Net-(D2-DO)") (class "Default")
      (node (ref "D2") (pin "2") (pinfunction "DO_2") (pintype "bidirectional"))
      (node (ref "D3") (pin "4") (pinfunction "DI_4") (pintype "bidirectional"))
    )
    (net (code "40") (name "Net-(D3-DO)") (class "Default")
      (node (ref "D3") (pin "2") (pinfunction "DO_2") (pintype "bidirectional"))
      (node (ref "D4") (pin "4") (pinfunction "DI_4") (pintype "bidirectional"))
    )
    (net (code "41") (name "Net-(D4-DO)") (class "Default")
      (node (ref "D4") (pin "2") (pinfunction "DO_2") (pintype "bidirectional"))
      (node (ref "D5") (pin "4") (pinfunction "DI_4") (pintype "bidirectional"))
    )
    (net (code "42") (name "Net-(D5-DO)") (class "Default")
      (node (ref "D5") (pin "2") (pinfunction "DO_2") (pintype "bidirectional"))
      (node (ref "D6") (pin "4") (pinfunction "DI_4") (pintype "bidirectional"))
    )
    (net (code "43") (name "Net-(D6-DO)") (class "Default")
      (node (ref "D6") (pin "2") (pinfunction "DO_2") (pintype "bidirectional"))
      (node (ref "D7") (pin "4") (pinfunction "DI_4") (pintype "bidirectional"))
    )
    (net (code "44") (name "Net-(D7-DO)") (class "Default")
      (node (ref "D7") (pin "2") (pinfunction "DO_2") (pintype "bidirectional"))
      (node (ref "D8") (pin "4") (pinfunction "DI_4") (pintype "bidirectional"))
    )
    (net (code "45") (name "Net-(D8-DO)") (class "Default")
      (node (ref "D8") (pin "2") (pinfunction "DO_2") (pintype "bidirectional"))
      (node (ref "D9") (pin "4") (pinfunction "DI_4") (pintype "bidirectional"))
    )
    (net (code "46") (name "Net-(D10-DI)") (class "Default")
      (node (ref "D10") (pin "4") (pinfunction "DI_4") (pintype "bidirectional"))
      (node (ref "D9") (pin "2") (pinfunction "DO_2") (pintype "bidirectional"))
    )
    (net (code "47") (name "Net-(D10-DO)") (class "Default")
      (node (ref "D10") (pin "2") (pinfunction "DO_2") (pintype "bidirectional"))
      (node (ref "D11") (pin "4") (pinfunction "DI_4") (pintype "bidirectional"))
    )
    (net (code "48") (name "Net-(D11-DO)") (class "Default")
      (node (ref "D11") (pin "2") (pinfunction "DO_2") (pintype "bidirectional"))
      (node (ref "D12") (pin "4") (pinfunction "DI_4") (pintype "bidirectional"))
    )
    (net (code "49") (name "Net-(D12-DO)") (class "Default")
      (node (ref "D12") (pin "2") (pinfunction "DO_2") (pintype "bidirectional"))
      (node (ref "D13") (pin "4") (pinfunction "DI_4") (pintype "bidirectional"))
    )
    (net (code "50") (name "Net-(D13-DO)") (class "Default")
      (node (ref "D13") (pin "2") (pinfunction "DO_2") (pintype "bidirectional"))
      (node (ref "D14") (pin "4") (pinfunction "DI_4") (pintype "bidirectional"))
    )
    (net (code "51") (name "Net-(D14-DO)") (class "Default")
      (node (ref "D14") (pin "2") (pinfunction "DO_2") (pintype "bidirectional"))
      (node (ref "D15") (pin "4") (pinfunction "DI_4") (pintype "bidirectional"))
    )
    (net (code "52") (name "Net-(D15-DO)") (class "Default")
      (node (ref "D15") (pin "2") (pinfunction "DO_2") (pintype "bidirectional"))
      (node (ref "D16") (pin "4") (pinfunction "DI_4") (pintype "bidirectional"))
    )
    (net (code "53") (name "Net-(D16-DO)") (class "Default")
      (node (ref "D16") (pin "2") (pinfunction "DO_2") (pintype "bidirectional"))
      (node (ref "D17") (pin "4") (pinfunction "DI_4") (pintype "bidirectional"))
    )
    (net (code "54") (name "Net-(D17-DO)") (class "Default")
      (node (ref "D17") (pin "2") (pinfunction "DO_2") (pintype "bidirectional"))
      (node (ref "D18") (pin "4") (pinfunction "DI_4") (pintype "bidirectional"))
    )
    (net (code "55") (name "Net-(D18-DO)") (class "Default")
      (node (ref "D18") (pin "2") (pinfunction "DO_2") (pintype "bidirectional"))
      (node (ref "D19") (pin "4") (pinfunction "DI_4") (pintype "bidirectional"))
    )
    (net (code "56") (name "Net-(D19-DO)") (class "Default")
      (node (ref "D19") (pin "2") (pinfunction "DO_2") (pintype "bidirectional"))
      (node (ref "D20") (pin "4") (pinfunction "DI_4") (pintype "bidirectional"))
    )
    (net (code "57") (name "Net-(D20-DO)") (class "Default")
      (node (ref "D20") (pin "2") (pinfunction "DO_2") (pintype "bidirectional"))
      (node (ref "D21") (pin "4") (pinfunction "DI_4") (pintype "bidirectional"))
    )
    (net (code "58") (name "Net-(D21-DO)") (class "Default")
      (node (ref "D21") (pin "2") (pinfunction "DO_2") (pintype "bidirectional"))
      (node (ref "D22") (pin "4") (pinfunction "DI_4") (pintype "bidirectional"))
    )
    (net (code "59") (name "Net-(D22-DO)") (class "Default")
      (node (ref "D22") (pin "2") (pinfunction "DO_2") (pintype "bidirectional"))
      (node (ref "D23") (pin "4") (pinfunction "DI_4") (pintype "bidirectional"))
    )
    (net (code "60") (name "Net-(D23-DO)") (class "Default")
      (node (ref "D23") (pin "2") (pinfunction "DO_2") (pintype "bidirectional"))
      (node (ref "D24") (pin "4") (pinfunction "DI_4") (pintype "bidirectional"))
    )
    (net (code "61") (name "Net-(D24-DO)") (class "Default")
      (node (ref "D24") (pin "2") (pinfunction "DO_2") (pintype "bidirectional"))
      (node (ref "D25") (pin "4") (pinfunction "DI_4") (pintype "bidirectional"))
    )
    (net (code "62") (name "Net-(D25-DO)") (class "Default")
      (node (ref "D25") (pin "2") (pinfunction "DO_2") (pintype "bidirectional"))
      (node (ref "D26") (pin "4") (pinfunction "DI_4") (pintype "bidirectional"))
    )
    (net (code "63") (name "Net-(D26-DO)") (class "Default")
      (node (ref "D26") (pin "2") (pinfunction "DO_2") (pintype "bidirectional"))
      (node (ref "D27") (pin "4") (pinfunction "DI_4") (pintype "bidirectional"))
    )
    (net (code "64") (name "Net-(D27-DO)") (class "Default")
      (node (ref "D27") (pin "2") (pinfunction "DO_2") (pintype "bidirectional"))
      (node (ref "D28") (pin "4") (pinfunction "DI_4") (pintype "bidirectional"))
    )
    (net (code "65") (name "Net-(D28-DO)") (class "Default")
      (node (ref "D28") (pin "2") (pinfunction "DO_2") (pintype "bidirectional"))
      (node (ref "D29") (pin "4") (pinfunction "DI_4") (pintype "bidirectional"))
    )
    (net (code "66") (name "Net-(D29-DO)") (class "Default")
      (node (ref "D29") (pin "2") (pinfunction "DO_2") (pintype "bidirectional"))
      (node (ref "D30") (pin "4") (pinfunction "DI_4") (pintype "bidirectional"))
    )
    (net (code "67") (name "Net-(D30-DO)") (class "Default")
      (node (ref "D30") (pin "2") (pinfunction "DO_2") (pintype "bidirectional"))
      (node (ref "D31") (pin "4") (pinfunction "DI_4") (pintype "bidirectional"))
    )
    (net (code "68") (name "Net-(D31-DO)") (class "Default")
      (node (ref "D31") (pin "2") (pinfunction "DO_2") (pintype "bidirectional"))
      (node (ref "D32") (pin "4") (pinfunction "DI_4") (pintype "bidirectional"))
    )
    (net (code "69") (name "Net-(D32-DO)") (class "Default")
      (node (ref "D32") (pin "2") (pinfunction "DO_2") (pintype "bidirectional"))
      (node (ref "D33") (pin "4") (pinfunction "DI_4") (pintype "bidirectional"))
    )
    (net (code "70") (name "Net-(D33-DO)") (class "Default")
      (node (ref "D33") (pin "2") (pinfunction "DO_2") (pintype "bidirectional"))
      (node (ref "D34") (pin "4") (pinfunction "DI_4") (pintype "bidirectional"))
    )
    (net (code "71") (name "Net-(D34-DO)") (class "Default")
      (node (ref "D34") (pin "2") (pinfunction "DO_2") (pintype "bidirectional"))
      (node (ref "D35") (pin "4") (pinfunction "DI_4") (pintype "bidirectional"))
    )
    (net (code "72") (name "Net-(D35-DO)") (class "Default")
      (node (ref "D35") (pin "2") (pinfunction "DO_2") (pintype "bidirectional"))
      (node (ref "D36") (pin "4") (pinfunction "DI_4") (pintype "bidirectional"))
    )
    (net (code "73") (name "Net-(D36-DO)") (class "Default")
      (node (ref "D36") (pin "2") (pinfunction "DO_2") (pintype "bidirectional"))
      (node (ref "D37") (pin "4") (pinfunction "DI_4") (pintype "bidirectional"))
    )
    (net (code "74") (name "Net-(D37-DO)") (class "Default")
      (node (ref "D37") (pin "2") (pinfunction "DO_2") (pintype "bidirectional"))
      (node (ref "D38") (pin "4") (pinfunction "DI_4") (pintype "bidirectional"))
    )
    (net (code "75") (name "Net-(D38-DO)") (class "Default")
      (node (ref "D38") (pin "2") (pinfunction "DO_2") (pintype "bidirectional"))
      (node (ref "D39") (pin "4") (pinfunction "DI_4") (pintype "bidirectional"))
    )
    (net (code "76") (name "Net-(D39-DO)") (class "Default")
      (node (ref "D39") (pin "2") (pinfunction "DO_2") (pintype "bidirectional"))
      (node (ref "D40") (pin "4") (pinfunction "DI_4") (pintype "bidirectional"))
    )
    (net (code "77") (name "Net-(D40-DO)") (class "Default")
      (node (ref "D40") (pin "2") (pinfunction "DO_2") (pintype "bidirectional"))
      (node (ref "D41") (pin "4") (pinfunction "DI_4") (pintype "bidirectional"))
    )
    (net (code "78") (name "Net-(D41-DO)") (class "Default")
      (node (ref "D41") (pin "2") (pinfunction "DO_2") (pintype "bidirectional"))
      (node (ref "D42") (pin "4") (pinfunction "DI_4") (pintype "bidirectional"))
    )
    (net (code "79") (name "Net-(D42-DO)") (class "Default")
      (node (ref "D42") (pin "2") (pinfunction "DO_2") (pintype "bidirectional"))
      (node (ref "D43") (pin "4") (pinfunction "DI_4") (pintype "bidirectional"))
    )
    (net (code "80") (name "Net-(D43-DO)") (class "Default")
      (node (ref "D43") (pin "2") (pinfunction "DO_2") (pintype "bidirectional"))
      (node (ref "D44") (pin "4") (pinfunction "DI_4") (pintype "bidirectional"))
    )
    (net (code "81") (name "Net-(D44-DO)") (class "Default")
      (node (ref "D44") (pin "2") (pinfunction "DO_2") (pintype "bidirectional"))
      (node (ref "D45") (pin "4") (pinfunction "DI_4") (pintype "bidirectional"))
    )
    (net (code "82") (name "Net-(D45-DO)") (class "Default")
      (node (ref "D45") (pin "2") (pinfunction "DO_2") (pintype "bidirectional"))
      (node (ref "D46") (pin "4") (pinfunction "DI_4") (pintype "bidirectional"))
    )
    (net (code "83") (name "Net-(D46-DO)") (class "Default")
      (node (ref "D46") (pin "2") (pinfunction "DO_2") (pintype "bidirectional"))
      (node (ref "D47") (pin "4") (pinfunction "DI_4") (pintype "bidirectional"))
    )
    (net (code "84") (name "Net-(D47-DO)") (class "Default")
      (node (ref "D47") (pin "2") (pinfunction "DO_2") (pintype "bidirectional"))
      (node (ref "D48") (pin "4") (pinfunction "DI_4") (pintype "bidirectional"))
    )
    (net (code "85") (name "Net-(D48-DO)") (class "Default")
      (node (ref "D48") (pin "2") (pinfunction "DO_2") (pintype "bidirectional"))
      (node (ref "D49") (pin "4") (pinfunction "DI_4") (pintype "bidirectional"))
    )
    (net (code "86") (name "Net-(D49-DO)") (class "Default")
      (node (ref "D49") (pin "2") (pinfunction "DO_2") (pintype "bidirectional"))
      (node (ref "D50") (pin "4") (pinfunction "DI_4") (pintype "bidirectional"))
    )
    (net (code "87") (name "Net-(D50-DO)") (class "Default")
      (node (ref "D50") (pin "2") (pinfunction "DO_2") (pintype "bidirectional"))
      (node (ref "D51") (pin "4") (pinfunction "DI_4") (pintype "bidirectional"))
    )
    (net (code "88") (name "Net-(D51-DO)") (class "Default")
      (node (ref "D51") (pin "2") (pinfunction "DO_2") (pintype "bidirectional"))
      (node (ref "D52") (pin "4") (pinfunction "DI_4") (pintype "bidirectional"))
    )
    (net (code "89") (name "Net-(D52-DO)") (class "Default")
      (node (ref "D52") (pin "2") (pinfunction "DO_2") (pintype "bidirectional"))
      (node (ref "D53") (pin "4") (pinfunction "DI_4") (pintype "bidirectional"))
    )
    (net (code "90") (name "Net-(D53-DO)") (class "Default")
      (node (ref "D53") (pin "2") (pinfunction "DO_2") (pintype "bidirectional"))
      (node (ref "D54") (pin "4") (pinfunction "DI_4") (pintype "bidirectional"))
    )
    (net (code "91") (name "Net-(D54-DO)") (class "Default")
      (node (ref "D54") (pin "2") (pinfunction "DO_2") (pintype "bidirectional"))
      (node (ref "D55") (pin "4") (pinfunction "DI_4") (pintype "bidirectional"))
    )
    (net (code "92") (name "Net-(D55-DO)") (class "Default")
      (node (ref "D55") (pin "2") (pinfunction "DO_2") (pintype "bidirectional"))
      (node (ref "D56") (pin "4") (pinfunction "DI_4") (pintype "bidirectional"))
    )
    (net (code "93") (name "Net-(D56-DO)") (class "Default")
      (node (ref "D56") (pin "2") (pinfunction "DO_2") (pintype "bidirectional"))
      (node (ref "D57") (pin "4") (pinfunction "DI_4") (pintype "bidirectional"))
    )
    (net (code "94") (name "Net-(D57-DO)") (class "Default")
      (node (ref "D57") (pin "2") (pinfunction "DO_2") (pintype "bidirectional"))
      (node (ref "D58") (pin "4") (pinfunction "DI_4") (pintype "bidirectional"))
    )
    (net (code "95") (name "Net-(D58-DO)") (class "Default")
      (node (ref "D58") (pin "2") (pinfunction "DO_2") (pintype "bidirectional"))
      (node (ref "D59") (pin "4") (pinfunction "DI_4") (pintype "bidirectional"))
    )
    (net (code "96") (name "Net-(D59-DO)") (class "Default")
      (node (ref "D59") (pin "2") (pinfunction "DO_2") (pintype "bidirectional"))
      (node (ref "D60") (pin "4") (pinfunction "DI_4") (pintype "bidirectional"))
    )
    (net (code "97") (name "Net-(D60-DO)") (class "Default")
      (node (ref "D60") (pin "2") (pinfunction "DO_2") (pintype "bidirectional"))
      (node (ref "D61") (pin "4") (pinfunction "DI_4") (pintype "bidirectional"))
    )
    (net (code "98") (name "Net-(D61-DO)") (class "Default")
      (node (ref "D61") (pin "2") (pinfunction "DO_2") (pintype "bidirectional"))
      (node (ref "D62") (pin "4") (pinfunction "DI_4") (pintype "bidirectional"))
    )
    (net (code "99") (name "Net-(D62-DO)") (class "Default")
      (node (ref "D62") (pin "2") (pinfunction "DO_2") (pintype "bidirectional"))
      (node (ref "D63") (pin "4") (pinfunction "DI_4") (pintype "bidirectional"))
    )
    (net (code "100") (name "Net-(D63-DO)") (class "Default")
      (node (ref "D63") (pin "2") (pinfunction "DO_2") (pintype "bidirectional"))
      (node (ref "D64") (pin "4") (pinfunction "DI_4") (pintype "bidirectional"))
    )
    (net (code "101") (name "Net-(D64-DO)") (class "Default")
      (node (ref "D64") (pin "2") (pinfunction "DO_2") (pintype "bidirectional"))
      (node (ref "D65") (pin "4") (pinfunction "DI_4") (pintype "bidirectional"))
    )
    (net (code "102") (name "Net-(D65-DO)") (class "Default")
      (node (ref "D65") (pin "2") (pinfunction "DO_2") (pintype "bidirectional"))
      (node (ref "D66") (pin "4") (pinfunction "DI_4") (pintype "bidirectional"))
    )
    (net (code "103") (name "Net-(D66-DO)") (class "Default")
      (node (ref "D66") (pin "2") (pinfunction "DO_2") (pintype "bidirectional"))
      (node (ref "D67") (pin "4") (pinfunction "DI_4") (pintype "bidirectional"))
    )
    (net (code "104") (name "Net-(D67-DO)") (class "Default")
      (node (ref "D67") (pin "2") (pinfunction "DO_2") (pintype "bidirectional"))
      (node (ref "D68") (pin "4") (pinfunction "DI_4") (pintype "bidirectional"))
    )
    (net (code "105") (name "Net-(D68-DO)") (class "Default")
      (node (ref "D68") (pin "2") (pinfunction "DO_2") (pintype "bidirectional"))
      (node (ref "D69") (pin "4") (pinfunction "DI_4") (pintype "bidirectional"))
    )
    (net (code "106") (name "Net-(D69-DO)") (class "Default")
      (node (ref "D69") (pin "2") (pinfunction "DO_2") (pintype "bidirectional"))
      (node (ref "D70") (pin "4") (pinfunction "DI_4") (pintype "bidirectional"))
    )
    (net (code "107") (name "Net-(D70-DO)") (class "Default")
      (node (ref "D70") (pin "2") (pinfunction "DO_2") (pintype "bidirectional"))
      (node (ref "D71") (pin "4") (pinfunction "DI_4") (pintype "bidirectional"))
    )
    (net (code "108") (name "Net-(D71-DO)") (class "Default")
      (node (ref "D71") (pin "2") (pinfunction "DO_2") (pintype "bidirectional"))
      (node (ref "D72") (pin "4") (pinfunction "DI_4") (pintype "bidirectional"))
    )
    (net (code "109") (name "Net-(D72-DO)") (class "Default")
      (node (ref "D72") (pin "2") (pinfunction "DO_2") (pintype "bidirectional"))
      (node (ref "D73") (pin "4") (pinfunction "DI_4") (pintype "bidirectional"))
    )
    (net (code "110") (name "Net-(D73-DO)") (class "Default")
      (node (ref "D73") (pin "2") (pinfunction "DO_2") (pintype "bidirectional"))
      (node (ref "D74") (pin "4") (pinfunction "DI_4") (pintype "bidirectional"))
    )
    (net (code "111") (name "Net-(D74-DO)") (class "Default")
      (node (ref "D74") (pin "2") (pinfunction "DO_2") (pintype "bidirectional"))
      (node (ref "D75") (pin "4") (pinfunction "DI_4") (pintype "bidirectional"))
    )
    (net (code "112") (name "Net-(D75-DO)") (class "Default")
      (node (ref "D75") (pin "2") (pinfunction "DO_2") (pintype "bidirectional"))
      (node (ref "D76") (pin "4") (pinfunction "DI_4") (pintype "bidirectional"))
    )
    (net (code "113") (name "Net-(D76-DO)") (class "Default")
      (node (ref "D76") (pin "2") (pinfunction "DO_2") (pintype "bidirectional"))
      (node (ref "D77") (pin "4") (pinfunction "DI_4") (pintype "bidirectional"))
    )
    (net (code "114") (name "Net-(D77-DO)") (class "Default")
      (node (ref "D77") (pin "2") (pinfunction "DO_2") (pintype "bidirectional"))
      (node (ref "D78") (pin "4") (pinfunction "DI_4") (pintype "bidirectional"))
    )
    (net (code "115") (name "Net-(D78-DO)") (class "Default")
      (node (ref "D78") (pin "2") (pinfunction "DO_2") (pintype "bidirectional"))
      (node (ref "D79") (pin "4") (pinfunction "DI_4") (pintype "bidirectional"))
    )
    (net (code "116") (name "Net-(D79-DO)") (class "Default")
      (node (ref "D79") (pin "2") (pinfunction "DO_2") (pintype "bidirectional"))
      (node (ref "D80") (pin "4") (pinfunction "DI_4") (pintype "bidirectional"))
    )
    (net (code "117") (name "Net-(D80-DO)") (class "Default")
      (node (ref "D80") (pin "2") (pinfunction "DO_2") (pintype "bidirectional"))
      (node (ref "D81") (pin "4") (pinfunction "DI_4") (pintype "bidirectional"))
    )
    (net (code "118") (name "Net-(D81-DO)") (class "Default")
      (node (ref "D81") (pin "2") (pinfunction "DO_2") (pintype "bidirectional"))
      (node (ref "D82") (pin "4") (pinfunction "DI_4") (pintype "bidirectional"))
    )
    (net (code "119") (name "Net-(D82-DO)") (class "Default")
      (node (ref "D82") (pin "2") (pinfunction "DO_2") (pintype "bidirectional"))
      (node (ref "D83") (pin "4") (pinfunction "DI_4") (pintype "bidirectional"))
    )
    (net (code "120") (name "Net-(D83-DO)") (class "Default")
      (node (ref "D83") (pin "2") (pinfunction "DO_2") (pintype "bidirectional"))
      (node (ref "D84") (pin "4") (pinfunction "DI_4") (pintype "bidirectional"))
    )
    (net (code "121") (name "Net-(D84-DO)") (class "Default")
      (node (ref "D84") (pin "2") (pinfunction "DO_2") (pintype "bidirectional"))
      (node (ref "D85") (pin "4") (pinfunction "DI_4") (pintype "bidirectional"))
    )
    (net (code "122") (name "Net-(D85-DO)") (class "Default")
      (node (ref "D85") (pin "2") (pinfunction "DO_2") (pintype "bidirectional"))
      (node (ref "D86") (pin "4") (pinfunction "DI_4") (pintype "bidirectional"))
    )
    (net (code "123") (name "Net-(D86-DO)") (class "Default")
      (node (ref "D86") (pin "2") (pinfunction "DO_2") (pintype "bidirectional"))
      (node (ref "D87") (pin "4") (pinfunction "DI_4") (pintype "bidirectional"))
    )
    (net (code "124") (name "Net-(D87-DO)") (class "Default")
      (node (ref "D87") (pin "2") (pinfunction "DO_2") (pintype "bidirectional"))
      (node (ref "D88") (pin "4") (pinfunction "DI_4") (pintype "bidirectional"))
    )
    (net (code "125") (name "Net-(D88-DO)") (class "Default")
      (node (ref "D88") (pin "2") (pinfunction "DO_2") (pintype "bidirectional"))
      (node (ref "D89") (pin "4") (pinfunction "DI_4") (pintype "bidirectional"))
    )
    (net (code "126") (name "Net-(D89-DO)") (class "Default")
      (node (ref "D89") (pin "2") (pinfunction "DO_2") (pintype "bidirectional"))
      (node (ref "D90") (pin "4") (pinfunction "DI_4") (pintype "bidirectional"))
    )
    (net (code "127") (name "Net-(R2-Pad2)") (class "Default")
      (node (ref "R2") (pin "2") (pinfunction "2_2") (pintype "passive"))
      (node (ref "T2") (pin "B") (pinfunction "B_B") (pintype "passive"))
    )
    (net (code "128") (name "Net-(R3-Pad2)") (class "Default")
      (node (ref "R3") (pin "2") (pinfunction "2_2") (pintype "passive"))
      (node (ref "T1") (pin "B") (pinfunction "B_B") (pintype "passive"))
    )
    (net (code "129") (name "VCC") (class "Default")
      (node (ref "C1") (pin "2") (pinfunction "2_2") (pintype "passive"))
      (node (ref "C10") (pin "2") (pinfunction "2_2") (pintype "passive"))
      (node (ref "C11") (pin "2") (pinfunction "2_2") (pintype "passive"))
      (node (ref "C12") (pin "2") (pinfunction "2_2") (pintype "passive"))
      (node (ref "C13") (pin "2") (pinfunction "2_2") (pintype "passive"))
      (node (ref "C14") (pin "2") (pinfunction "2_2") (pintype "passive"))
      (node (ref "C15") (pin "2") (pinfunction "2_2") (pintype "passive"))
      (node (ref "C16") (pin "2") (pinfunction "2_2") (pintype "passive"))
      (node (ref "C17") (pin "2") (pinfunction "2_2") (pintype "passive"))
      (node (ref "C18") (pin "2") (pinfunction "2_2") (pintype "passive"))
      (node (ref "C19") (pin "2") (pinfunction "2_2") (pintype "passive"))
      (node (ref "C2") (pin "2") (pinfunction "2_2") (pintype "passive"))
      (node (ref "C20") (pin "2") (pinfunction "2_2") (pintype "passive"))
      (node (ref "C21") (pin "2") (pinfunction "2_2") (pintype "passive"))
      (node (ref "C22") (pin "2") (pinfunction "2_2") (pintype "passive"))
      (node (ref "C23") (pin "2") (pinfunction "2_2") (pintype "passive"))
      (node (ref "C24") (pin "2") (pinfunction "2_2") (pintype "passive"))
      (node (ref "C25") (pin "2") (pinfunction "2_2") (pintype "passive"))
      (node (ref "C26") (pin "2") (pinfunction "2_2") (pintype "passive"))
      (node (ref "C27") (pin "2") (pinfunction "2_2") (pintype "passive"))
      (node (ref "C28") (pin "2") (pinfunction "2_2") (pintype "passive"))
      (node (ref "C29") (pin "2") (pinfunction "2_2") (pintype "passive"))
      (node (ref "C3") (pin "2") (pinfunction "2_2") (pintype "passive"))
      (node (ref "C30") (pin "2") (pinfunction "2_2") (pintype "passive"))
      (node (ref "C31") (pin "2") (pinfunction "2_2") (pintype "passive"))
      (node (ref "C32") (pin "2") (pinfunction "2_2") (pintype "passive"))
      (node (ref "C33") (pin "2") (pinfunction "2_2") (pintype "passive"))
      (node (ref "C34") (pin "2") (pinfunction "2_2") (pintype "passive"))
      (node (ref "C35") (pin "2") (pinfunction "2_2") (pintype "passive"))
      (node (ref "C36") (pin "2") (pinfunction "2_2") (pintype "passive"))
      (node (ref "C37") (pin "2") (pinfunction "2_2") (pintype "passive"))
      (node (ref "C38") (pin "2") (pinfunction "2_2") (pintype "passive"))
      (node (ref "C39") (pin "2") (pinfunction "2_2") (pintype "passive"))
      (node (ref "C4") (pin "2") (pinfunction "2_2") (pintype "passive"))
      (node (ref "C40") (pin "2") (pinfunction "2_2") (pintype "passive"))
      (node (ref "C41") (pin "2") (pinfunction "2_2") (pintype "passive"))
      (node (ref "C42") (pin "2") (pinfunction "2_2") (pintype "passive"))
      (node (ref "C43") (pin "2") (pinfunction "2_2") (pintype "passive"))
      (node (ref "C44") (pin "2") (pinfunction "2_2") (pintype "passive"))
      (node (ref "C45") (pin "2") (pinfunction "2_2") (pintype "passive"))
      (node (ref "C46") (pin "2") (pinfunction "2_2") (pintype "passive"))
      (node (ref "C47") (pin "2") (pinfunction "2_2") (pintype "passive"))
      (node (ref "C48") (pin "2") (pinfunction "2_2") (pintype "passive"))
      (node (ref "C49") (pin "2") (pinfunction "2_2") (pintype "passive"))
      (node (ref "C5") (pin "2") (pinfunction "2_2") (pintype "passive"))
      (node (ref "C50") (pin "2") (pinfunction "2_2") (pintype "passive"))
      (node (ref "C51") (pin "2") (pinfunction "2_2") (pintype "passive"))
      (node (ref "C52") (pin "2") (pinfunction "2_2") (pintype "passive"))
      (node (ref "C53") (pin "2") (pinfunction "2_2") (pintype "passive"))
      (node (ref "C54") (pin "2") (pinfunction "2_2") (pintype "passive"))
      (node (ref "C55") (pin "2") (pinfunction "2_2") (pintype "passive"))
      (node (ref "C56") (pin "2") (pinfunction "2_2") (pintype "passive"))
      (node (ref "C57") (pin "2") (pinfunction "2_2") (pintype "passive"))
      (node (ref "C58") (pin "2") (pinfunction "2_2") (pintype "passive"))
      (node (ref "C59") (pin "2") (pinfunction "2_2") (pintype "passive"))
      (node (ref "C6") (pin "2") (pinfunction "2_2") (pintype "passive"))
      (node (ref "C60") (pin "2") (pinfunction "2_2") (pintype "passive"))
      (node (ref "C61") (pin "2") (pinfunction "2_2") (pintype "passive"))
      (node (ref "C62") (pin "2") (pinfunction "2_2") (pintype "passive"))
      (node (ref "C63") (pin "2") (pinfunction "2_2") (pintype "passive"))
      (node (ref "C64") (pin "2") (pinfunction "2_2") (pintype "passive"))
      (node (ref "C65") (pin "2") (pinfunction "2_2") (pintype "passive"))
      (node (ref "C66") (pin "2") (pinfunction "2_2") (pintype "passive"))
      (node (ref "C67") (pin "2") (pinfunction "2_2") (pintype "passive"))
      (node (ref "C68") (pin "2") (pinfunction "2_2") (pintype "passive"))
      (node (ref "C69") (pin "2") (pinfunction "2_2") (pintype "passive"))
      (node (ref "C7") (pin "2") (pinfunction "2_2") (pintype "passive"))
      (node (ref "C70") (pin "2") (pinfunction "2_2") (pintype "passive"))
      (node (ref "C71") (pin "2") (pinfunction "2_2") (pintype "passive"))
      (node (ref "C72") (pin "2") (pinfunction "2_2") (pintype "passive"))
      (node (ref "C73") (pin "2") (pinfunction "2_2") (pintype "passive"))
      (node (ref "C74") (pin "2") (pinfunction "2_2") (pintype "passive"))
      (node (ref "C75") (pin "2") (pinfunction "2_2") (pintype "passive"))
      (node (ref "C76") (pin "2") (pinfunction "2_2") (pintype "passive"))
      (node (ref "C77") (pin "2") (pinfunction "2_2") (pintype "passive"))
      (node (ref "C78") (pin "2") (pinfunction "2_2") (pintype "passive"))
      (node (ref "C79") (pin "2") (pinfunction "2_2") (pintype "passive"))
      (node (ref "C8") (pin "2") (pinfunction "2_2") (pintype "passive"))
      (node (ref "C80") (pin "2") (pinfunction "2_2") (pintype "passive"))
      (node (ref "C81") (pin "2") (pinfunction "2_2") (pintype "passive"))
      (node (ref "C82") (pin "2") (pinfunction "2_2") (pintype "passive"))
      (node (ref "C83") (pin "2") (pinfunction "2_2") (pintype "passive"))
      (node (ref "C84") (pin "2") (pinfunction "2_2") (pintype "passive"))
      (node (ref "C85") (pin "2") (pinfunction "2_2") (pintype "passive"))
      (node (ref "C86") (pin "2") (pinfunction "2_2") (pintype "passive"))
      (node (ref "C87") (pin "2") (pinfunction "2_2") (pintype "passive"))
      (node (ref "C88") (pin "2") (pinfunction "2_2") (pintype "passive"))
      (node (ref "C89") (pin "2") (pinfunction "2_2") (pintype "passive"))
      (node (ref "C9") (pin "2") (pinfunction "2_2") (pintype "passive"))
      (node (ref "C90") (pin "2") (pinfunction "2_2") (pintype "passive"))
      (node (ref "C91") (pin "1") (pinfunction "1_1") (pintype "passive"))
      (node (ref "D1") (pin "1") (pinfunction "VDD_1") (pintype "bidirectional"))
      (node (ref "D10") (pin "1") (pinfunction "VDD_1") (pintype "bidirectional"))
      (node (ref "D11") (pin "1") (pinfunction "VDD_1") (pintype "bidirectional"))
      (node (ref "D12") (pin "1") (pinfunction "VDD_1") (pintype "bidirectional"))
      (node (ref "D13") (pin "1") (pinfunction "VDD_1") (pintype "bidirectional"))
      (node (ref "D14") (pin "1") (pinfunction "VDD_1") (pintype "bidirectional"))
      (node (ref "D15") (pin "1") (pinfunction "VDD_1") (pintype "bidirectional"))
      (node (ref "D16") (pin "1") (pinfunction "VDD_1") (pintype "bidirectional"))
      (node (ref "D17") (pin "1") (pinfunction "VDD_1") (pintype "bidirectional"))
      (node (ref "D18") (pin "1") (pinfunction "VDD_1") (pintype "bidirectional"))
      (node (ref "D19") (pin "1") (pinfunction "VDD_1") (pintype "bidirectional"))
      (node (ref "D2") (pin "1") (pinfunction "VDD_1") (pintype "bidirectional"))
      (node (ref "D20") (pin "1") (pinfunction "VDD_1") (pintype "bidirectional"))
      (node (ref "D21") (pin "1") (pinfunction "VDD_1") (pintype "bidirectional"))
      (node (ref "D22") (pin "1") (pinfunction "VDD_1") (pintype "bidirectional"))
      (node (ref "D23") (pin "1") (pinfunction "VDD_1") (pintype "bidirectional"))
      (node (ref "D24") (pin "1") (pinfunction "VDD_1") (pintype "bidirectional"))
      (node (ref "D25") (pin "1") (pinfunction "VDD_1") (pintype "bidirectional"))
      (node (ref "D26") (pin "1") (pinfunction "VDD_1") (pintype "bidirectional"))
      (node (ref "D27") (pin "1") (pinfunction "VDD_1") (pintype "bidirectional"))
      (node (ref "D28") (pin "1") (pinfunction "VDD_1") (pintype "bidirectional"))
      (node (ref "D29") (pin "1") (pinfunction "VDD_1") (pintype "bidirectional"))
      (node (ref "D3") (pin "1") (pinfunction "VDD_1") (pintype "bidirectional"))
      (node (ref "D30") (pin "1") (pinfunction "VDD_1") (pintype "bidirectional"))
      (node (ref "D31") (pin "1") (pinfunction "VDD_1") (pintype "bidirectional"))
      (node (ref "D32") (pin "1") (pinfunction "VDD_1") (pintype "bidirectional"))
      (node (ref "D33") (pin "1") (pinfunction "VDD_1") (pintype "bidirectional"))
      (node (ref "D34") (pin "1") (pinfunction "VDD_1") (pintype "bidirectional"))
      (node (ref "D35") (pin "1") (pinfunction "VDD_1") (pintype "bidirectional"))
      (node (ref "D36") (pin "1") (pinfunction "VDD_1") (pintype "bidirectional"))
      (node (ref "D37") (pin "1") (pinfunction "VDD_1") (pintype "bidirectional"))
      (node (ref "D38") (pin "1") (pinfunction "VDD_1") (pintype "bidirectional"))
      (node (ref "D39") (pin "1") (pinfunction "VDD_1") (pintype "bidirectional"))
      (node (ref "D4") (pin "1") (pinfunction "VDD_1") (pintype "bidirectional"))
      (node (ref "D40") (pin "1") (pinfunction "VDD_1") (pintype "bidirectional"))
      (node (ref "D41") (pin "1") (pinfunction "VDD_1") (pintype "bidirectional"))
      (node (ref "D42") (pin "1") (pinfunction "VDD_1") (pintype "bidirectional"))
      (node (ref "D43") (pin "1") (pinfunction "VDD_1") (pintype "bidirectional"))
      (node (ref "D44") (pin "1") (pinfunction "VDD_1") (pintype "bidirectional"))
      (node (ref "D45") (pin "1") (pinfunction "VDD_1") (pintype "bidirectional"))
      (node (ref "D46") (pin "1") (pinfunction "VDD_1") (pintype "bidirectional"))
      (node (ref "D47") (pin "1") (pinfunction "VDD_1") (pintype "bidirectional"))
      (node (ref "D48") (pin "1") (pinfunction "VDD_1") (pintype "bidirectional"))
      (node (ref "D49") (pin "1") (pinfunction "VDD_1") (pintype "bidirectional"))
      (node (ref "D5") (pin "1") (pinfunction "VDD_1") (pintype "bidirectional"))
      (node (ref "D50") (pin "1") (pinfunction "VDD_1") (pintype "bidirectional"))
      (node (ref "D51") (pin "1") (pinfunction "VDD_1") (pintype "bidirectional"))
      (node (ref "D52") (pin "1") (pinfunction "VDD_1") (pintype "bidirectional"))
      (node (ref "D53") (pin "1") (pinfunction "VDD_1") (pintype "bidirectional"))
      (node (ref "D54") (pin "1") (pinfunction "VDD_1") (pintype "bidirectional"))
      (node (ref "D55") (pin "1") (pinfunction "VDD_1") (pintype "bidirectional"))
      (node (ref "D56") (pin "1") (pinfunction "VDD_1") (pintype "bidirectional"))
      (node (ref "D57") (pin "1") (pinfunction "VDD_1") (pintype "bidirectional"))
      (node (ref "D58") (pin "1") (pinfunction "VDD_1") (pintype "bidirectional"))
      (node (ref "D59") (pin "1") (pinfunction "VDD_1") (pintype "bidirectional"))
      (node (ref "D6") (pin "1") (pinfunction "VDD_1") (pintype "bidirectional"))
      (node (ref "D60") (pin "1") (pinfunction "VDD_1") (pintype "bidirectional"))
      (node (ref "D61") (pin "1") (pinfunction "VDD_1") (pintype "bidirectional"))
      (node (ref "D62") (pin "1") (pinfunction "VDD_1") (pintype "bidirectional"))
      (node (ref "D63") (pin "1") (pinfunction "VDD_1") (pintype "bidirectional"))
      (node (ref "D64") (pin "1") (pinfunction "VDD_1") (pintype "bidirectional"))
      (node (ref "D65") (pin "1") (pinfunction "VDD_1") (pintype "bidirectional"))
      (node (ref "D66") (pin "1") (pinfunction "VDD_1") (pintype "bidirectional"))
      (node (ref "D67") (pin "1") (pinfunction "VDD_1") (pintype "bidirectional"))
      (node (ref "D68") (pin "1") (pinfunction "VDD_1") (pintype "bidirectional"))
      (node (ref "D69") (pin "1") (pinfunction "VDD_1") (pintype "bidirectional"))
      (node (ref "D7") (pin "1") (pinfunction "VDD_1") (pintype "bidirectional"))
      (node (ref "D70") (pin "1") (pinfunction "VDD_1") (pintype "bidirectional"))
      (node (ref "D71") (pin "1") (pinfunction "VDD_1") (pintype "bidirectional"))
      (node (ref "D72") (pin "1") (pinfunction "VDD_1") (pintype "bidirectional"))
      (node (ref "D73") (pin "1") (pinfunction "VDD_1") (pintype "bidirectional"))
      (node (ref "D74") (pin "1") (pinfunction "VDD_1") (pintype "bidirectional"))
      (node (ref "D75") (pin "1") (pinfunction "VDD_1") (pintype "bidirectional"))
      (node (ref "D76") (pin "1") (pinfunction "VDD_1") (pintype "bidirectional"))
      (node (ref "D77") (pin "1") (pinfunction "VDD_1") (pintype "bidirectional"))
      (node (ref "D78") (pin "1") (pinfunction "VDD_1") (pintype "bidirectional"))
      (node (ref "D79") (pin "1") (pinfunction "VDD_1") (pintype "bidirectional"))
      (node (ref "D8") (pin "1") (pinfunction "VDD_1") (pintype "bidirectional"))
      (node (ref "D80") (pin "1") (pinfunction "VDD_1") (pintype "bidirectional"))
      (node (ref "D81") (pin "1") (pinfunction "VDD_1") (pintype "bidirectional"))
      (node (ref "D82") (pin "1") (pinfunction "VDD_1") (pintype "bidirectional"))
      (node (ref "D83") (pin "1") (pinfunction "VDD_1") (pintype "bidirectional"))
      (node (ref "D84") (pin "1") (pinfunction "VDD_1") (pintype "bidirectional"))
      (node (ref "D85") (pin "1") (pinfunction "VDD_1") (pintype "bidirectional"))
      (node (ref "D86") (pin "1") (pinfunction "VDD_1") (pintype "bidirectional"))
      (node (ref "D87") (pin "1") (pinfunction "VDD_1") (pintype "bidirectional"))
      (node (ref "D88") (pin "1") (pinfunction "VDD_1") (pintype "bidirectional"))
      (node (ref "D89") (pin "1") (pinfunction "VDD_1") (pintype "bidirectional"))
      (node (ref "D9") (pin "1") (pinfunction "VDD_1") (pintype "bidirectional"))
      (node (ref "D90") (pin "1") (pinfunction "VDD_1") (pintype "bidirectional"))
      (node (ref "IC1") (pin "3") (pinfunction "VIN_3") (pintype "input"))
      (node (ref "VCC") (pin "1") (pinfunction "P_1") (pintype "passive"))
      (node (ref "VIN") (pin "1") (pinfunction "P_1") (pintype "passive"))
    )
    (net (code "130") (name "unconnected-(D90-DO-Pad2)") (class "Default")
      (node (ref "D90") (pin "2") (pinfunction "DO_2") (pintype "bidirectional"))
    )
  )
)
